# OpenROV_Controller_2_6.net
KiCad netlist of a schematic drawn in EAGLE
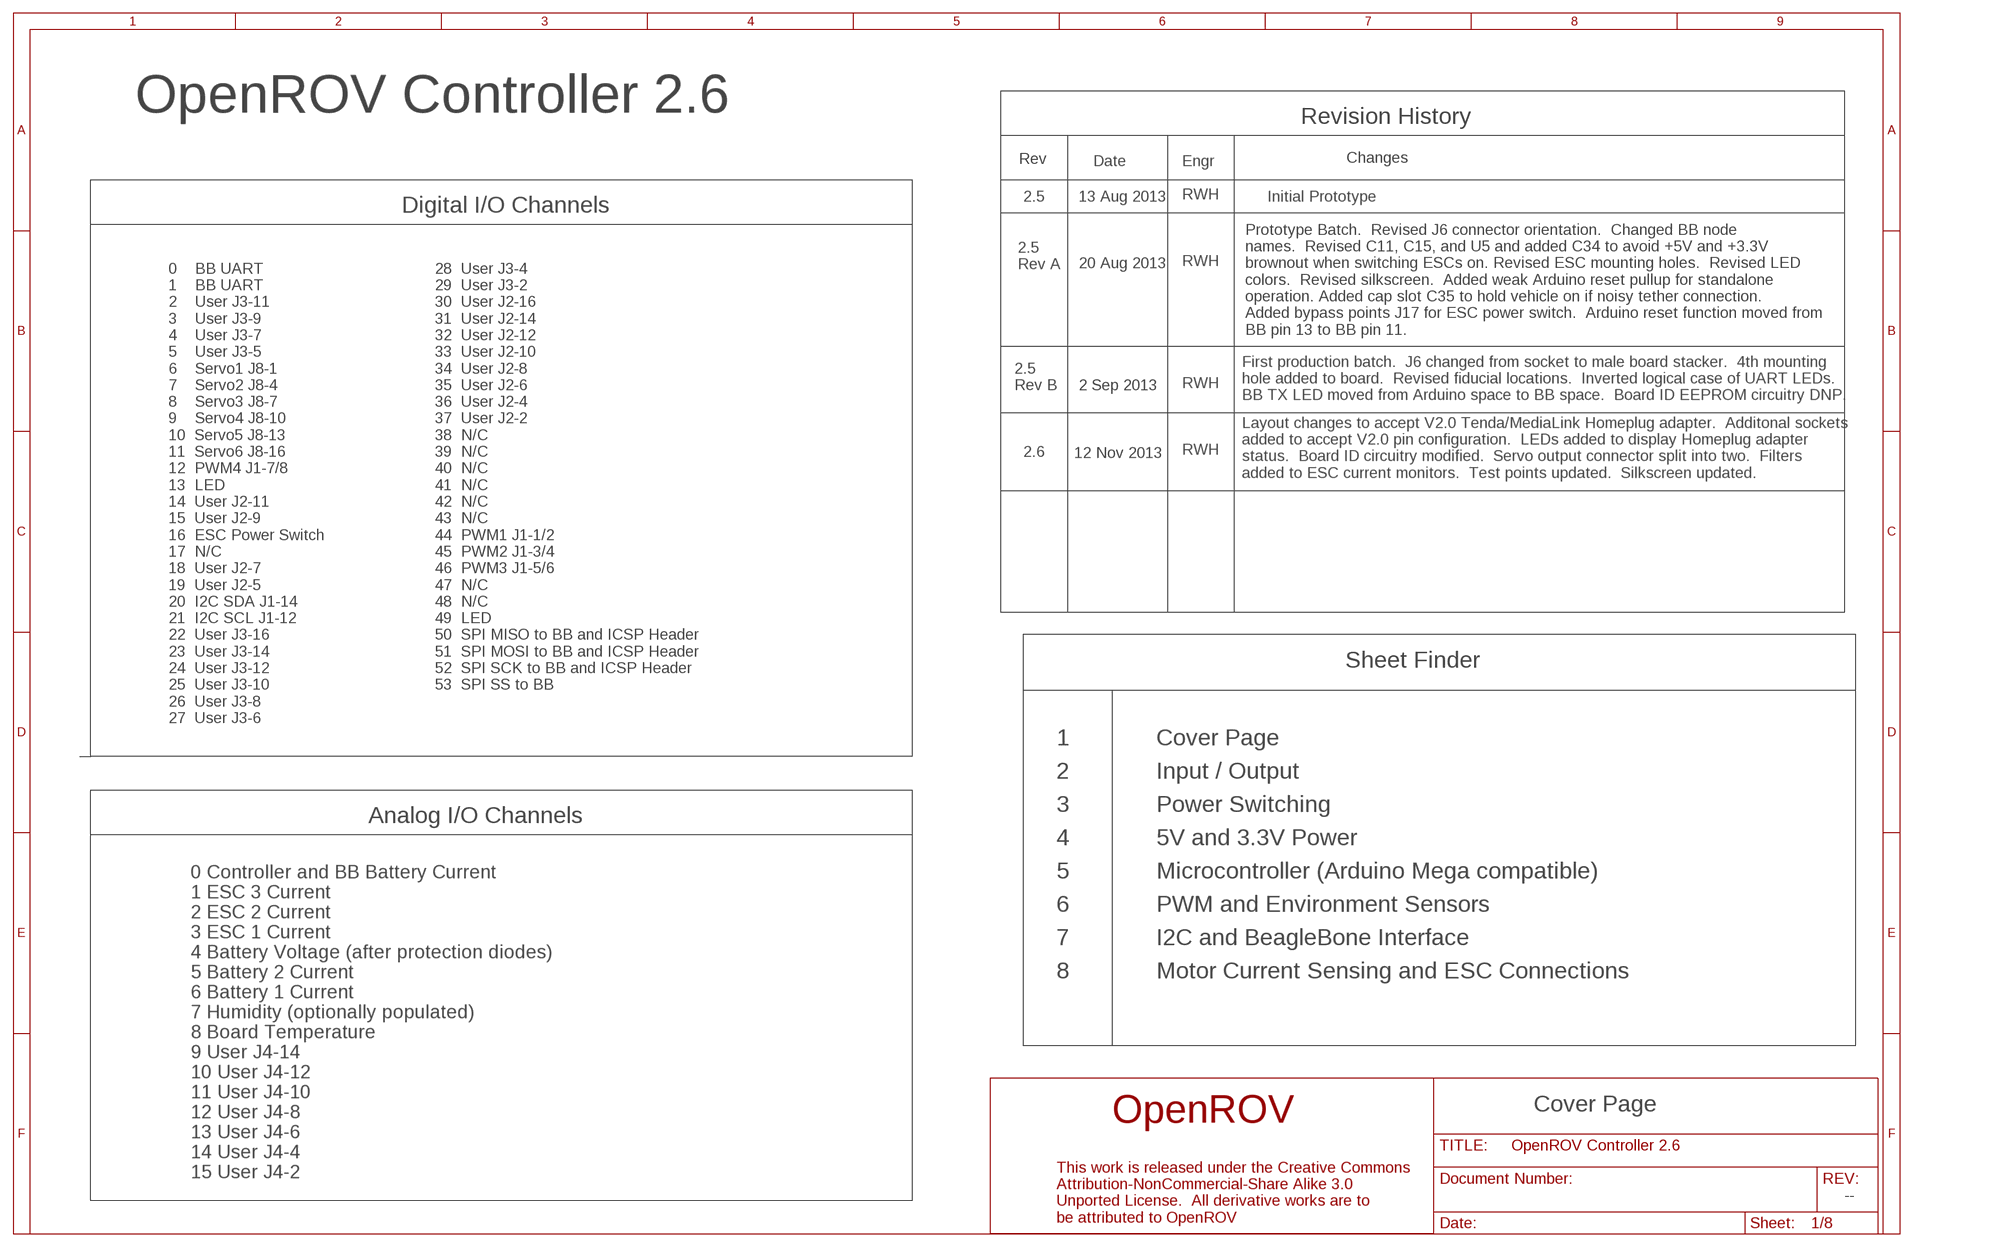
[diagram p0: schematic, sheet 1]
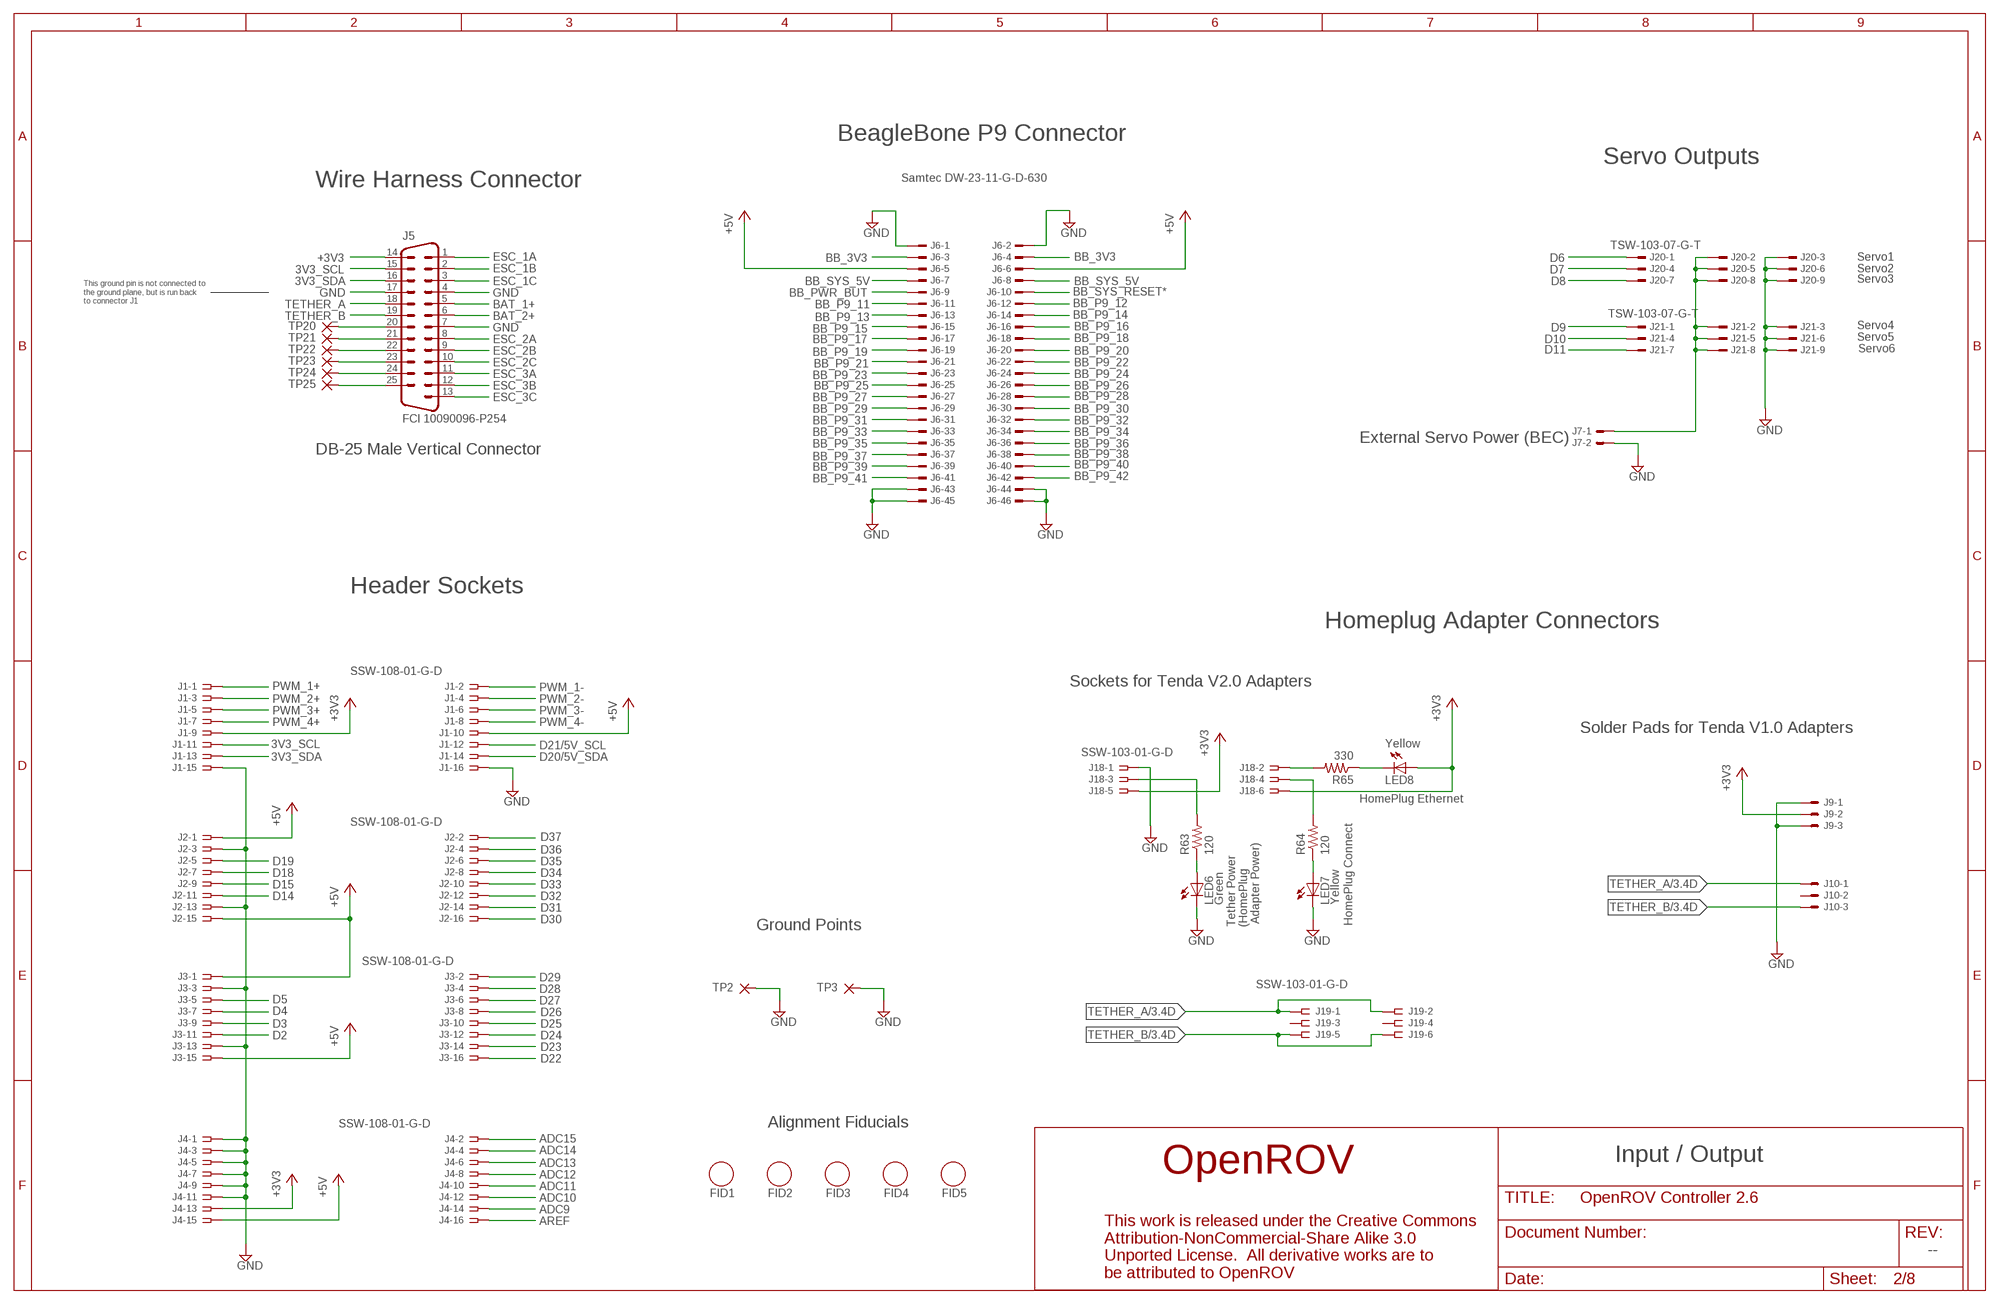
[diagram p1: schematic, sheet 2]
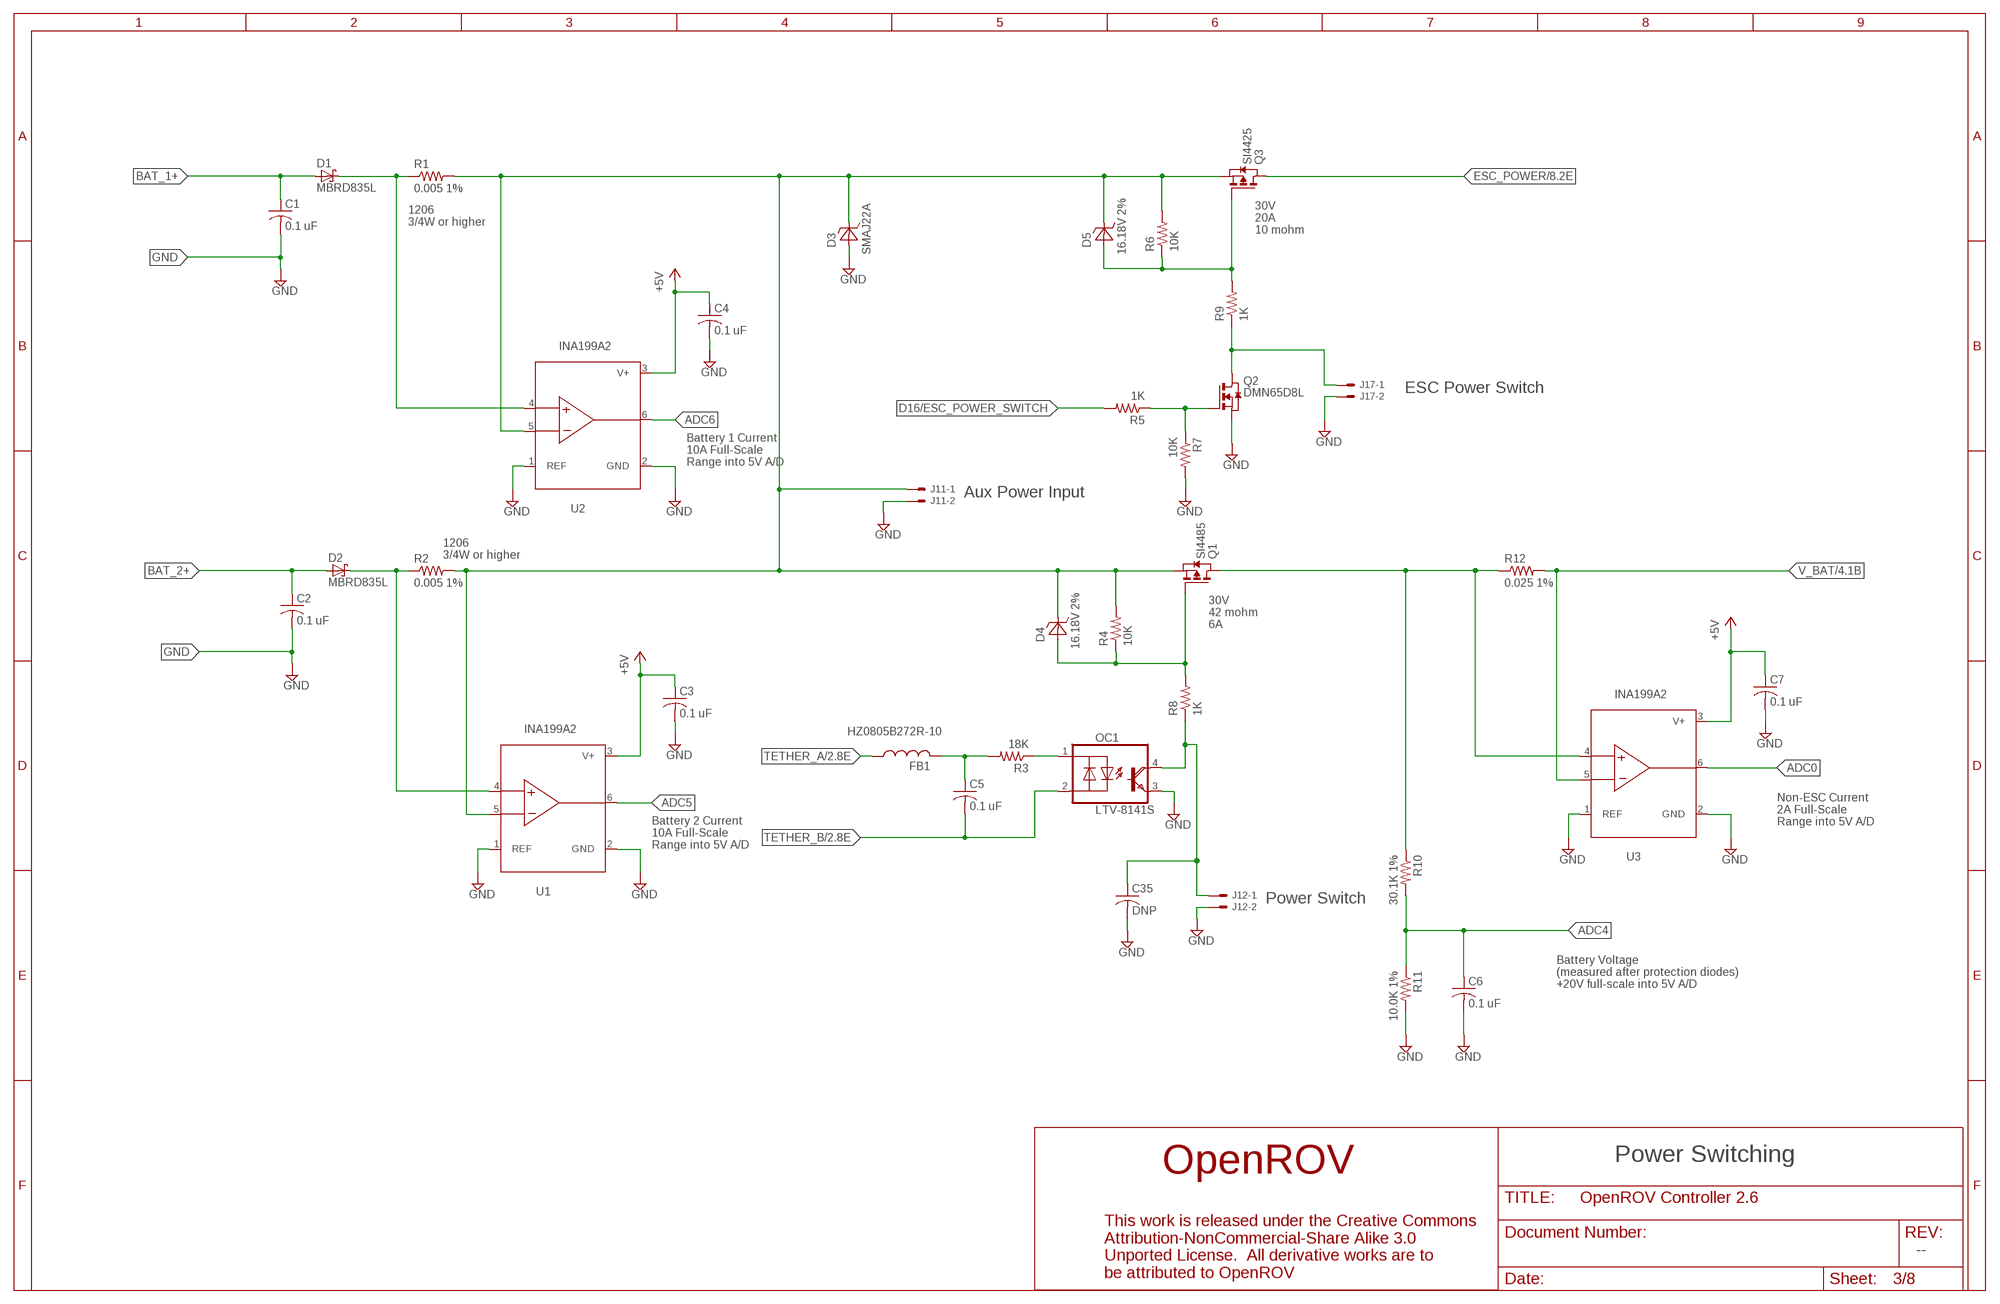
[diagram p2: schematic, sheet 3]
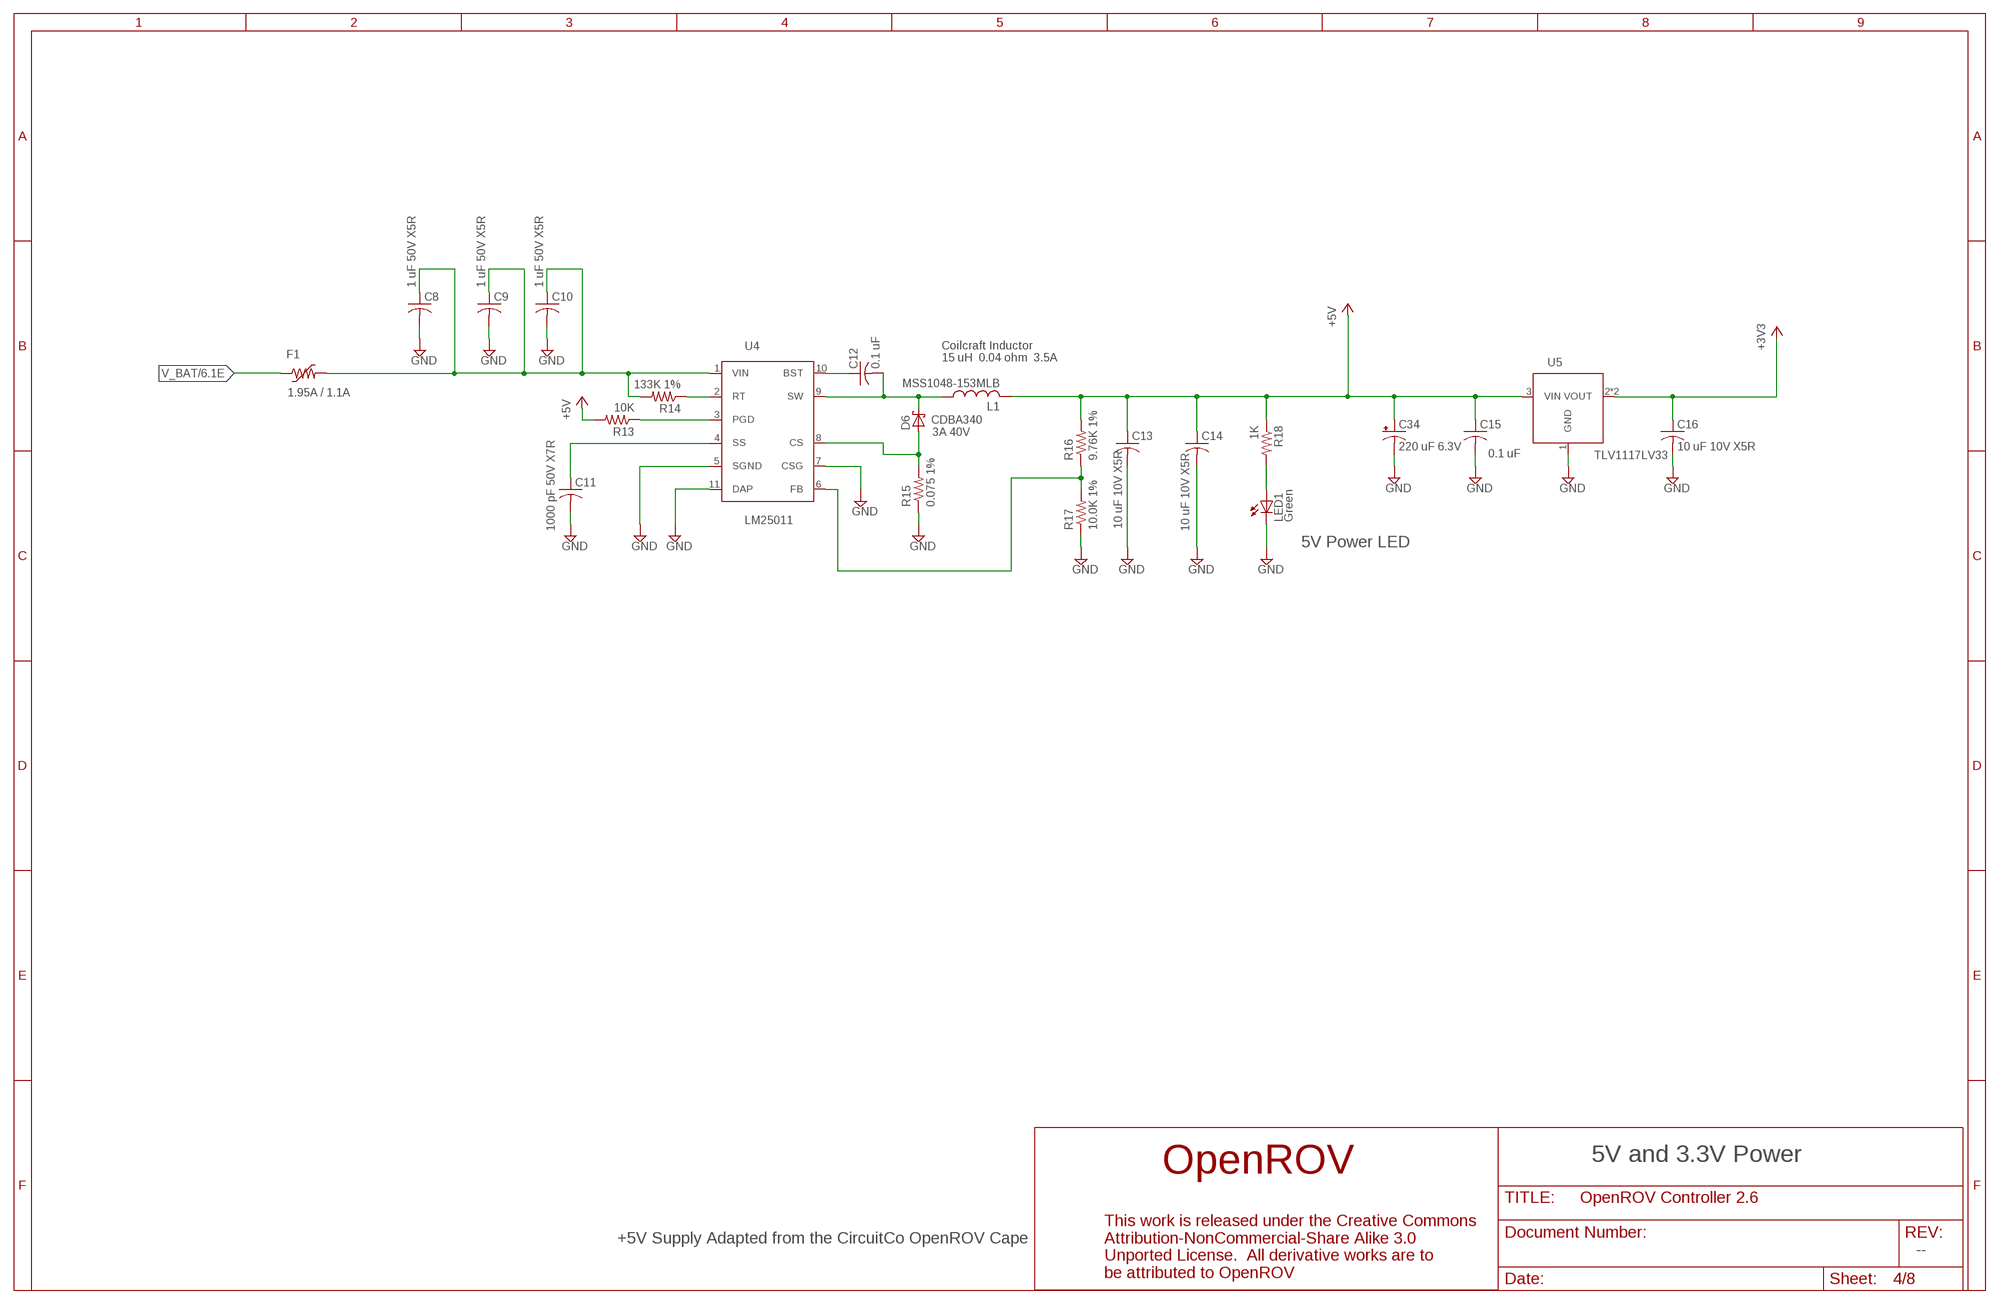
[diagram p3: schematic, sheet 4]
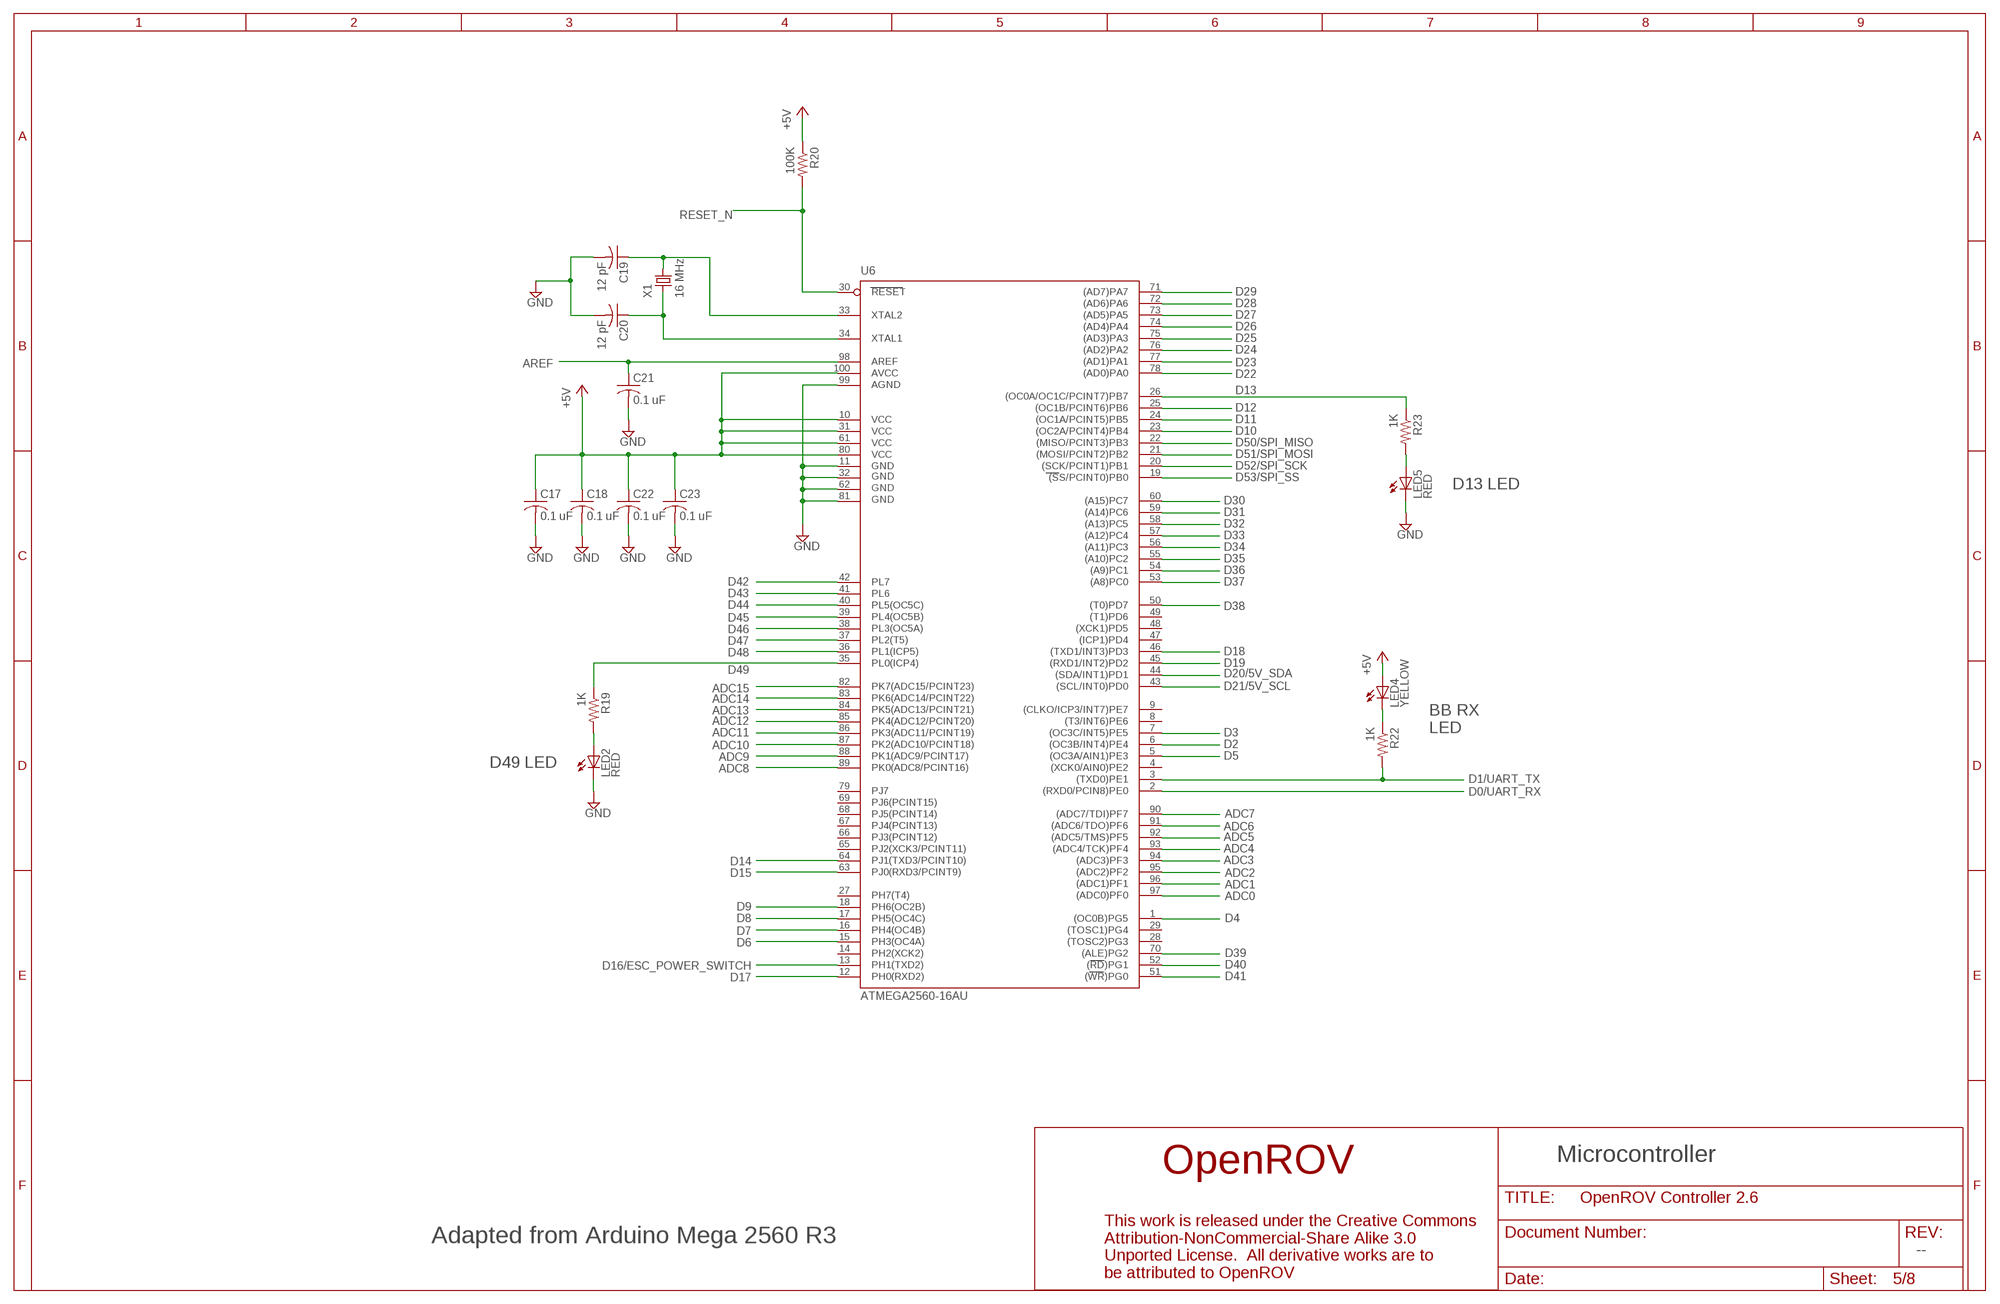
[diagram p4: schematic, sheet 5]
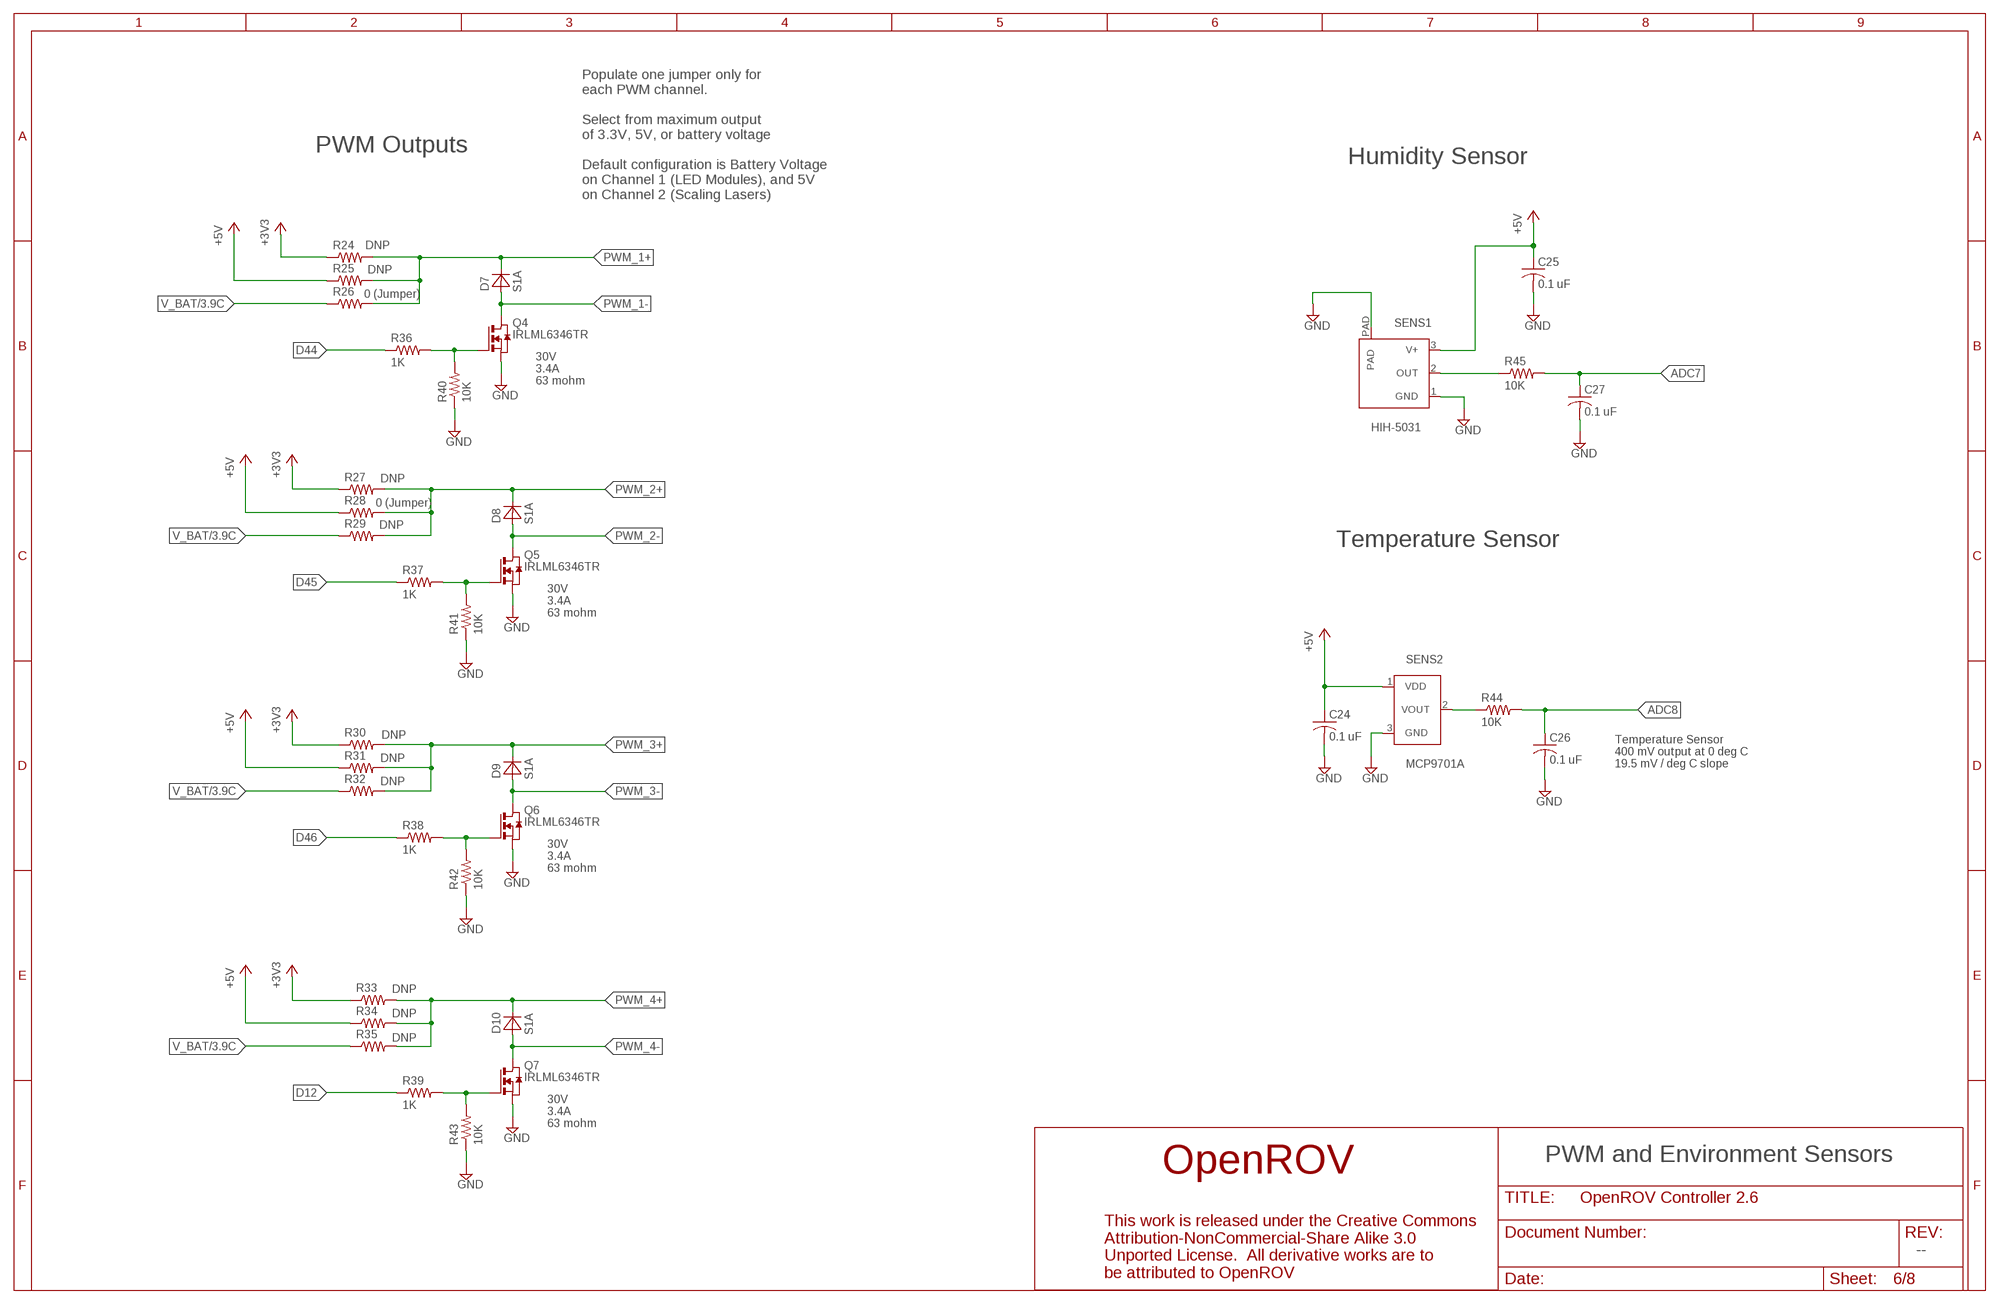
[diagram p5: schematic, sheet 6]
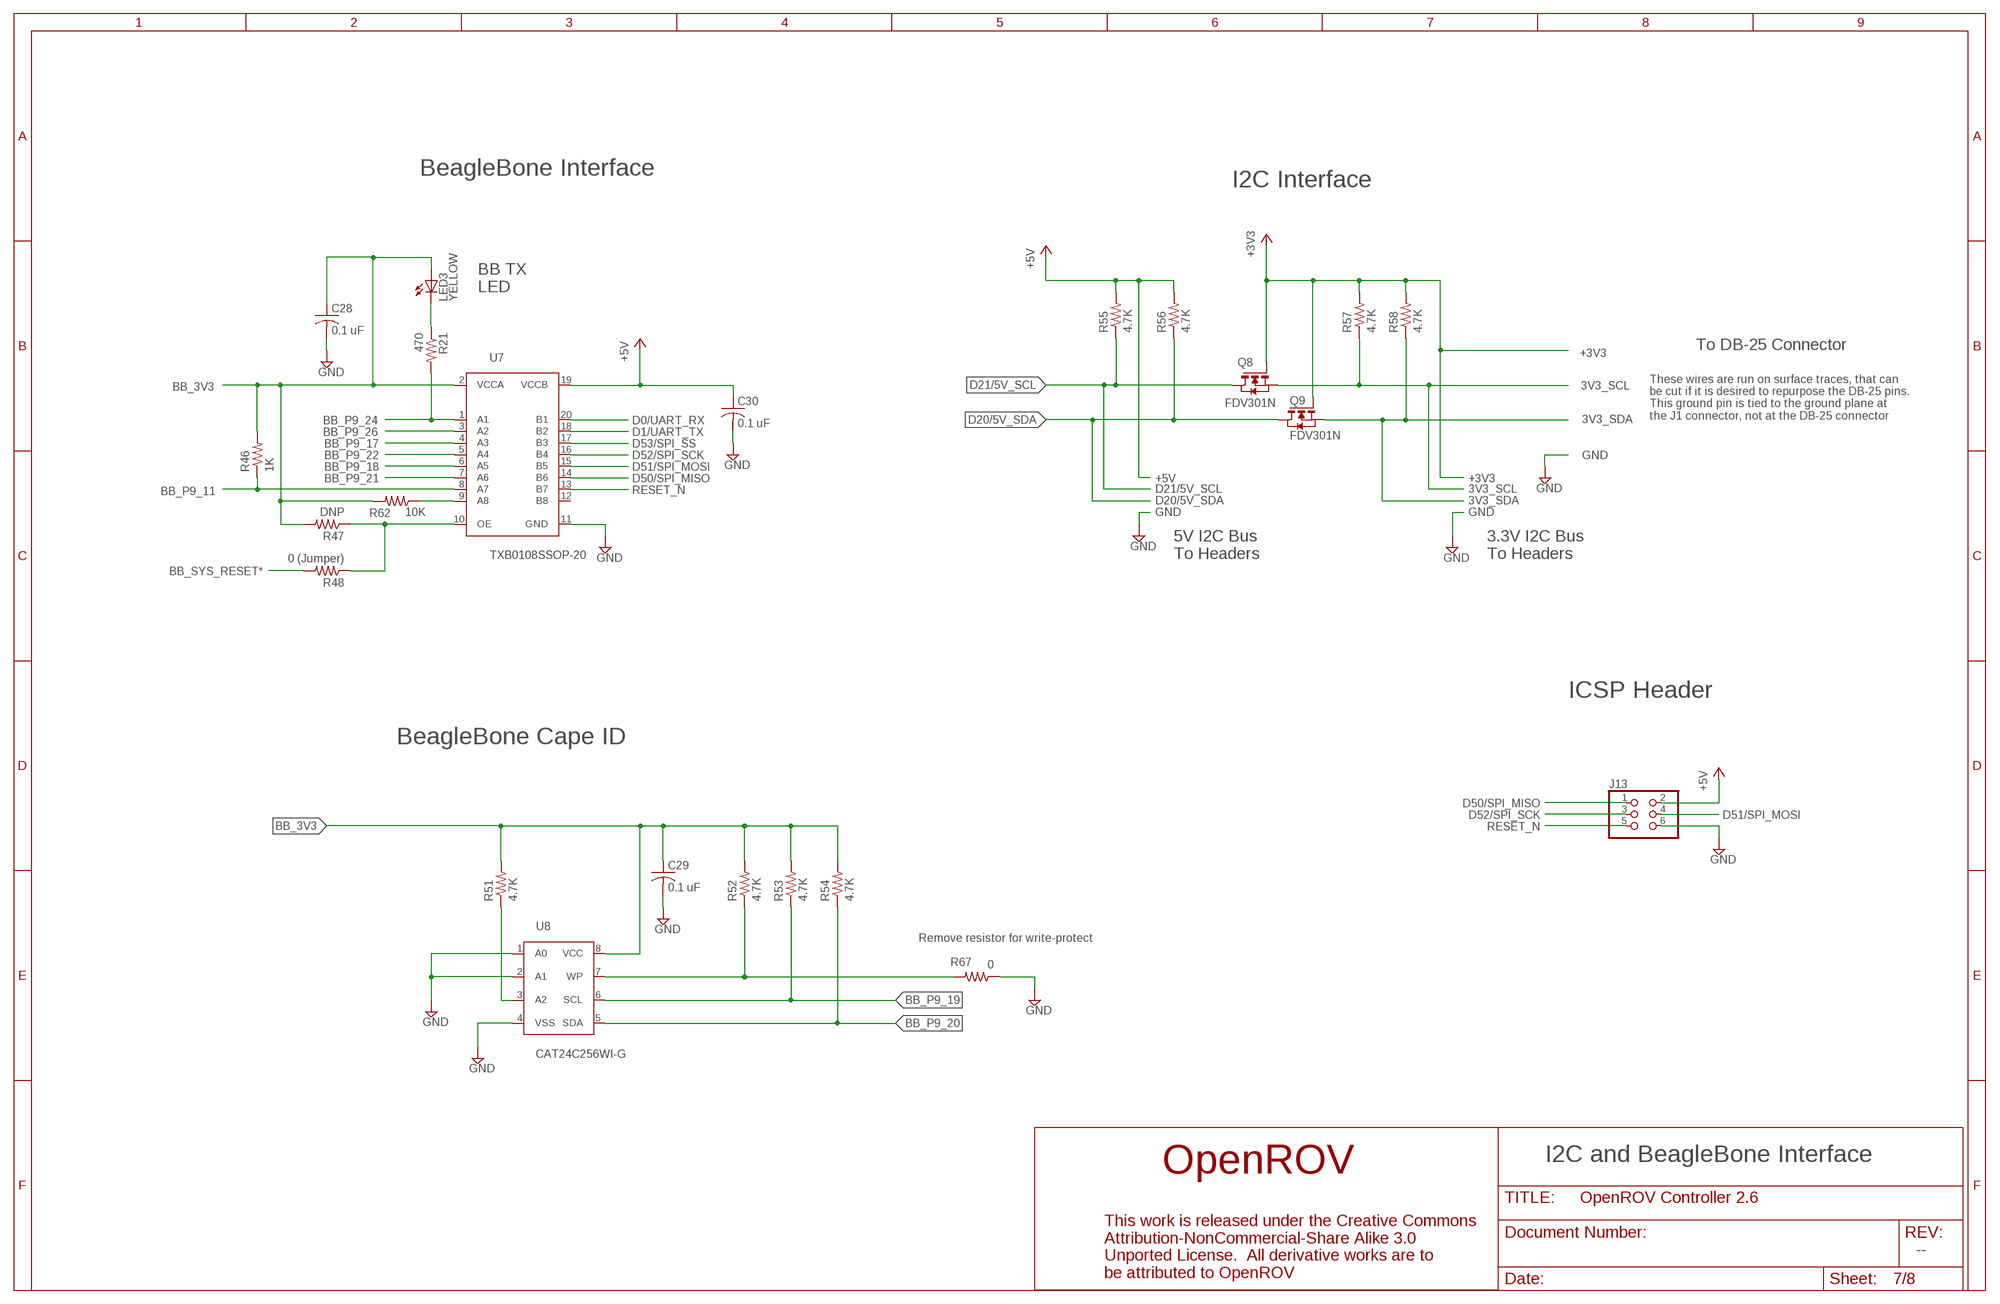
[diagram p6: schematic, sheet 7]
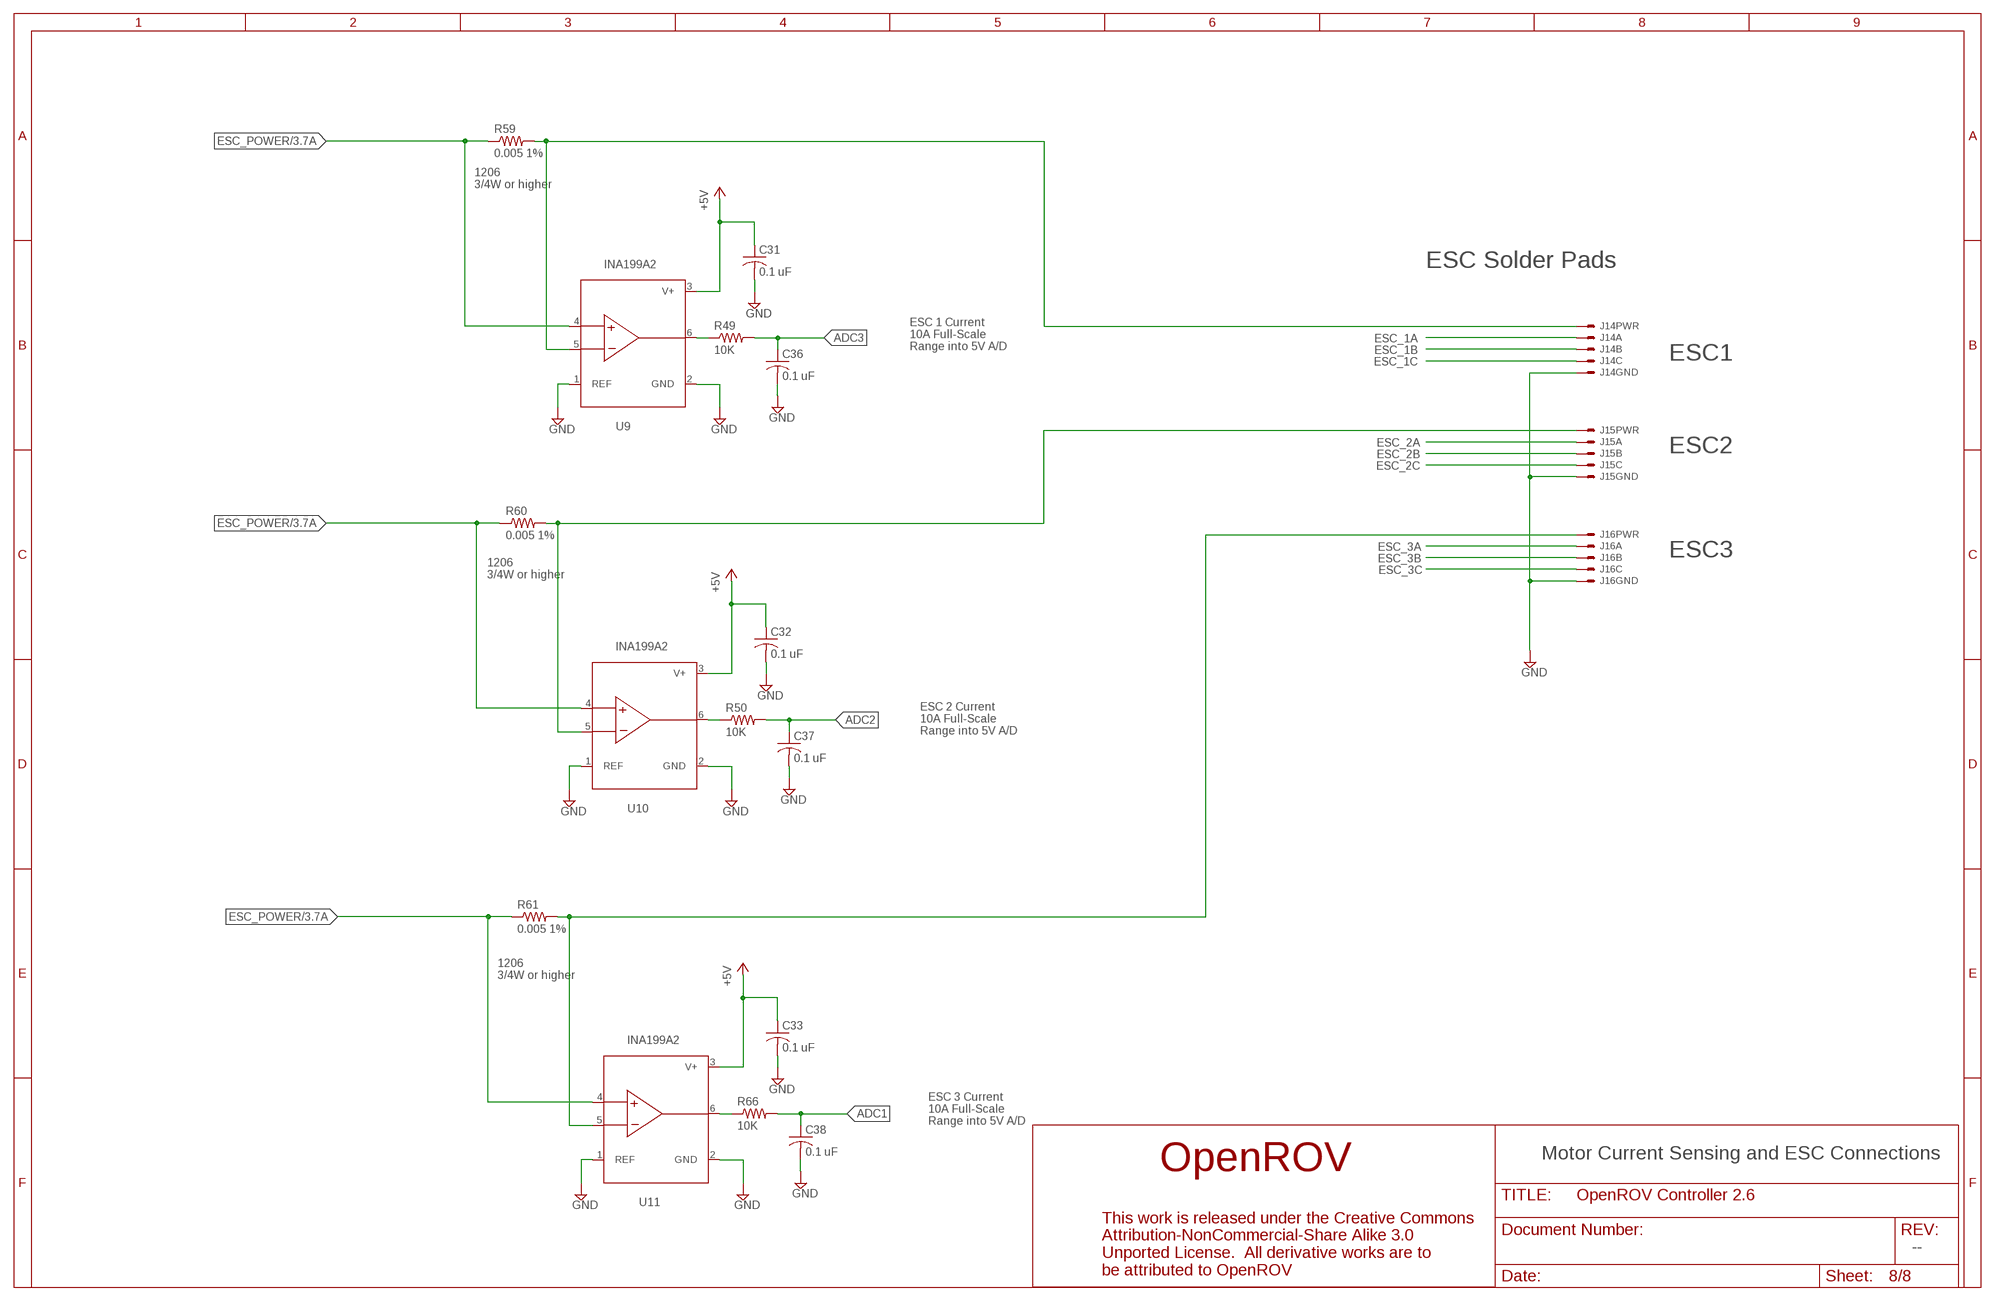
[diagram p7: schematic, sheet 8]

(export (version "E")
  (design (tool "Eeschema 10.0.6"))
  (components
    (comp (ref "FID1")
      (value "FIDUCIAL_1")
      (footprint "eagle-import:FIDUCIAL_1")
      (libsource (lib "eagle-import") (part "FIDUCIAL_1"))
    )
    (comp (ref "FID2")
      (value "FIDUCIAL_1")
      (footprint "eagle-import:FIDUCIAL_1")
      (libsource (lib "eagle-import") (part "FIDUCIAL_1"))
    )
    (comp (ref "FID3")
      (value "FIDUCIAL_1")
      (footprint "eagle-import:FIDUCIAL_1")
      (libsource (lib "eagle-import") (part "FIDUCIAL_1"))
    )
    (comp (ref "FID4")
      (value "FIDUCIAL_1")
      (footprint "eagle-import:FIDUCIAL_1")
      (libsource (lib "eagle-import") (part "FIDUCIAL_1"))
    )
    (comp (ref "FID5")
      (value "FIDUCIAL_1")
      (footprint "eagle-import:FIDUCIAL_1")
      (libsource (lib "eagle-import") (part "FIDUCIAL_1"))
    )
    (comp (ref "J1")
      (value "SSW-108-01-G-D")
      (footprint "eagle-import:SSW-108-02-S-D")
      (fields (field (name "MPN") "SSW-108-02-S-D"))
      (libsource (lib "eagle-import") (part "HDR_SOCKET_2X8"))
    )
    (comp (ref "J2")
      (value "SSW-108-01-G-D")
      (footprint "eagle-import:SSW-108-02-S-D")
      (fields (field (name "MPN") "SSW-108-02-S-D"))
      (libsource (lib "eagle-import") (part "HDR_SOCKET_2X8"))
    )
    (comp (ref "J3")
      (value "SSW-108-01-G-D")
      (footprint "eagle-import:SSW-108-02-S-D")
      (fields (field (name "MPN") "SSW-108-02-S-D"))
      (libsource (lib "eagle-import") (part "HDR_SOCKET_2X8"))
    )
    (comp (ref "J4")
      (value "SSW-108-01-G-D")
      (footprint "eagle-import:SSW-108-02-S-D")
      (fields (field (name "MPN") "SSW-108-02-S-D"))
      (libsource (lib "eagle-import") (part "HDR_SOCKET_2X8"))
    )
    (comp (ref "J5")
      (value "FCI 10090096-P254")
      (footprint "eagle-import:M25VP")
      (libsource (lib "eagle-import") (part "M25VP"))
    )
    (comp (ref "J6")
      (value "Samtec DW-23-11-G-D-630")
      (footprint "eagle-import:TSW-123-02-S-D")
      (libsource (lib "eagle-import") (part "BEAGLEBONE_PIN_HEADER"))
    )
    (comp (ref "J7")
      (value "HDR_1X2X0.100-ALT_SILK")
      (footprint "eagle-import:22-23-2021_ALT_SILK")
      (libsource (lib "eagle-import") (part "HDR_1X2X0.100-ALT_SILK"))
    )
    (comp (ref "J9")
      (value "HDR_1X3X0.100-ALT_SILK")
      (footprint "eagle-import:22-23-2031_ALT_SILK")
      (libsource (lib "eagle-import") (part "HDR_1X3X0.100-ALT_SILK"))
    )
    (comp (ref "J10")
      (value "HDR_1X3X0.100-ALT_SILK")
      (footprint "eagle-import:22-23-2031_ALT_SILK")
      (libsource (lib "eagle-import") (part "HDR_1X3X0.100-ALT_SILK"))
    )
    (comp (ref "J18")
      (value "SSW-103-01-G-D")
      (footprint "eagle-import:SSW-103-02-S-D")
      (fields (field (name "MPN") "SSW-103-02-S-D"))
      (libsource (lib "eagle-import") (part "HDR_SOCKET_2X3"))
    )
    (comp (ref "J19")
      (value "SSW-103-01-G-D")
      (footprint "eagle-import:SSW-103-02-S-D")
      (fields (field (name "MPN") "SSW-103-02-S-D"))
      (libsource (lib "eagle-import") (part "HDR_SOCKET_2X3"))
    )
    (comp (ref "J20")
      (value "TSW-103-07-G-T")
      (footprint "eagle-import:HDR_PINS_3X3")
      (libsource (lib "eagle-import") (part "HDR_PINS_3X3{dblquote}"))
    )
    (comp (ref "J21")
      (value "TSW-103-07-G-T")
      (footprint "eagle-import:HDR_PINS_3X3")
      (libsource (lib "eagle-import") (part "HDR_PINS_3X3{dblquote}"))
    )
    (comp (ref "LED6")
      (value "Green")
      (footprint "eagle-import:LED_CHIPLED_0603")
      (libsource (lib "eagle-import") (part "LED-0603"))
    )
    (comp (ref "LED7")
      (value "Yellow")
      (footprint "eagle-import:LED_CHIPLED_0603")
      (libsource (lib "eagle-import") (part "LED-0603"))
    )
    (comp (ref "LED8")
      (value "Yellow")
      (footprint "eagle-import:LED_CHIPLED_0603")
      (libsource (lib "eagle-import") (part "LED-0603"))
    )
    (comp (ref "R63")
      (value "120")
      (footprint "eagle-import:R0603")
      (libsource (lib "eagle-import") (part "RESISTOR-0603"))
    )
    (comp (ref "R64")
      (value "120")
      (footprint "eagle-import:R0603")
      (libsource (lib "eagle-import") (part "RESISTOR-0603"))
    )
    (comp (ref "R65")
      (value "330")
      (footprint "eagle-import:R0603")
      (libsource (lib "eagle-import") (part "RESISTOR-0603"))
    )
    (comp (ref "TP2")
      (value "TEST_PAD-1.0")
      (footprint "eagle-import:2.0_1.0")
      (libsource (lib "eagle-import") (part "TEST_PAD-1.0"))
    )
    (comp (ref "TP3")
      (value "TEST_PAD-1.0")
      (footprint "eagle-import:2.0_1.0")
      (libsource (lib "eagle-import") (part "TEST_PAD-1.0"))
    )
    (comp (ref "TP20")
      (value "TEST_PAD-1.0")
      (footprint "eagle-import:2.0_1.0")
      (libsource (lib "eagle-import") (part "TEST_PAD-1.0"))
    )
    (comp (ref "TP21")
      (value "TEST_PAD-1.0")
      (footprint "eagle-import:2.0_1.0")
      (libsource (lib "eagle-import") (part "TEST_PAD-1.0"))
    )
    (comp (ref "TP22")
      (value "TEST_PAD-1.0")
      (footprint "eagle-import:2.0_1.0")
      (libsource (lib "eagle-import") (part "TEST_PAD-1.0"))
    )
    (comp (ref "TP23")
      (value "TEST_PAD-1.0")
      (footprint "eagle-import:2.0_1.0")
      (libsource (lib "eagle-import") (part "TEST_PAD-1.0"))
    )
    (comp (ref "TP24")
      (value "TEST_PAD-1.0")
      (footprint "eagle-import:2.0_1.0")
      (libsource (lib "eagle-import") (part "TEST_PAD-1.0"))
    )
    (comp (ref "TP25")
      (value "TEST_PAD-1.0")
      (footprint "eagle-import:2.0_1.0")
      (libsource (lib "eagle-import") (part "TEST_PAD-1.0"))
    )
    (comp (ref "C1")
      (value "0.1 uF")
      (footprint "eagle-import:R0603")
      (libsource (lib "eagle-import") (part "CAP0603"))
    )
    (comp (ref "C2")
      (value "0.1 uF")
      (footprint "eagle-import:R0603")
      (libsource (lib "eagle-import") (part "CAP0603"))
    )
    (comp (ref "C3")
      (value "0.1 uF")
      (footprint "eagle-import:R0603")
      (libsource (lib "eagle-import") (part "CAP0603"))
    )
    (comp (ref "C4")
      (value "0.1 uF")
      (footprint "eagle-import:R0603")
      (libsource (lib "eagle-import") (part "CAP0603"))
    )
    (comp (ref "C5")
      (value "0.1 uF")
      (footprint "eagle-import:R0603")
      (libsource (lib "eagle-import") (part "CAP0603"))
    )
    (comp (ref "C6")
      (value "0.1 uF")
      (footprint "eagle-import:R0603")
      (libsource (lib "eagle-import") (part "CAP0603"))
    )
    (comp (ref "C7")
      (value "0.1 uF")
      (footprint "eagle-import:R0603")
      (libsource (lib "eagle-import") (part "CAP0603"))
    )
    (comp (ref "C35")
      (value "DNP")
      (footprint "eagle-import:R0805")
      (libsource (lib "eagle-import") (part "CAP0805"))
    )
    (comp (ref "D1")
      (value "MBRD835L")
      (footprint "eagle-import:DPAK")
      (libsource (lib "eagle-import") (part "SCHOTTKYDPAK"))
    )
    (comp (ref "D2")
      (value "MBRD835L")
      (footprint "eagle-import:DPAK")
      (libsource (lib "eagle-import") (part "SCHOTTKYDPAK"))
    )
    (comp (ref "D3")
      (value "SMAJ22A")
      (footprint "eagle-import:DO214AC")
      (libsource (lib "eagle-import") (part "ZENER-TVSDO-214AC"))
    )
    (comp (ref "D4")
      (value "16.18V 2%")
      (footprint "eagle-import:SOD323")
      (libsource (lib "eagle-import") (part "ZENER-TVSSOD323"))
    )
    (comp (ref "D5")
      (value "16.18V 2%")
      (footprint "eagle-import:SOD323")
      (libsource (lib "eagle-import") (part "ZENER-TVSSOD323"))
    )
    (comp (ref "FB1")
      (value "HZ0805B272R-10")
      (footprint "eagle-import:R0805")
      (libsource (lib "eagle-import") (part "FERRITESIZE_0805"))
    )
    (comp (ref "J11")
      (value "HDR_1X2X0.100-ALT_SILK")
      (footprint "eagle-import:22-23-2021_ALT_SILK")
      (libsource (lib "eagle-import") (part "HDR_1X2X0.100-ALT_SILK"))
    )
    (comp (ref "J12")
      (value "HDR_1X2X0.100-ALT_SILK")
      (footprint "eagle-import:22-23-2021_ALT_SILK")
      (libsource (lib "eagle-import") (part "HDR_1X2X0.100-ALT_SILK"))
    )
    (comp (ref "J17")
      (value "HDR_1X2X0.100-ALT_SILK")
      (footprint "eagle-import:22-23-2021_ALT_SILK")
      (libsource (lib "eagle-import") (part "HDR_1X2X0.100-ALT_SILK"))
    )
    (comp (ref "OC1")
      (value "LTV-8141S")
      (footprint "eagle-import:DIL4-SMD")
      (libsource (lib "eagle-import") (part "LTV-8141S"))
    )
    (comp (ref "Q1")
      (value "SI4485")
      (footprint "eagle-import:SO8")
      (libsource (lib "eagle-import") (part "PMOS-FET"))
    )
    (comp (ref "Q2")
      (value "DMN65D8L")
      (footprint "eagle-import:SOT23")
      (libsource (lib "eagle-import") (part "NMOS-FETSOT23"))
    )
    (comp (ref "Q3")
      (value "SI4425")
      (footprint "eagle-import:SO8")
      (libsource (lib "eagle-import") (part "PMOS-FET"))
    )
    (comp (ref "R1")
      (value "0.005 1%")
      (footprint "eagle-import:R1206")
      (libsource (lib "eagle-import") (part "RESISTOR-1206"))
    )
    (comp (ref "R2")
      (value "0.005 1%")
      (footprint "eagle-import:R1206")
      (libsource (lib "eagle-import") (part "RESISTOR-1206"))
    )
    (comp (ref "R3")
      (value "18K")
      (footprint "eagle-import:R0603")
      (libsource (lib "eagle-import") (part "RESISTOR-0603"))
    )
    (comp (ref "R4")
      (value "10K")
      (footprint "eagle-import:R0603")
      (libsource (lib "eagle-import") (part "RESISTOR-0603"))
    )
    (comp (ref "R5")
      (value "1K")
      (footprint "eagle-import:R0603")
      (libsource (lib "eagle-import") (part "RESISTOR-0603"))
    )
    (comp (ref "R6")
      (value "10K")
      (footprint "eagle-import:R0603")
      (libsource (lib "eagle-import") (part "RESISTOR-0603"))
    )
    (comp (ref "R7")
      (value "10K")
      (footprint "eagle-import:R0603")
      (libsource (lib "eagle-import") (part "RESISTOR-0603"))
    )
    (comp (ref "R8")
      (value "1K")
      (footprint "eagle-import:R0603")
      (libsource (lib "eagle-import") (part "RESISTOR-0603"))
    )
    (comp (ref "R9")
      (value "1K")
      (footprint "eagle-import:R0603")
      (libsource (lib "eagle-import") (part "RESISTOR-0603"))
    )
    (comp (ref "R10")
      (value "30.1K 1%")
      (footprint "eagle-import:R0603")
      (libsource (lib "eagle-import") (part "RESISTOR-0603"))
    )
    (comp (ref "R11")
      (value "10.0K 1%")
      (footprint "eagle-import:R0603")
      (libsource (lib "eagle-import") (part "RESISTOR-0603"))
    )
    (comp (ref "R12")
      (value "0.025 1%")
      (footprint "eagle-import:R0805")
      (libsource (lib "eagle-import") (part "RESISTOR-0805"))
    )
    (comp (ref "U1")
      (value "INA199A2")
      (footprint "eagle-import:SC70-6L")
      (libsource (lib "eagle-import") (part "INA199"))
    )
    (comp (ref "U2")
      (value "INA199A2")
      (footprint "eagle-import:SC70-6L")
      (libsource (lib "eagle-import") (part "INA199"))
    )
    (comp (ref "U3")
      (value "INA199A2")
      (footprint "eagle-import:SC70-6L")
      (libsource (lib "eagle-import") (part "INA199"))
    )
    (comp (ref "C31")
      (value "0.1 uF")
      (footprint "eagle-import:R0603")
      (libsource (lib "eagle-import") (part "CAP0603"))
    )
    (comp (ref "C32")
      (value "0.1 uF")
      (footprint "eagle-import:R0603")
      (libsource (lib "eagle-import") (part "CAP0603"))
    )
    (comp (ref "C33")
      (value "0.1 uF")
      (footprint "eagle-import:R0603")
      (libsource (lib "eagle-import") (part "CAP0603"))
    )
    (comp (ref "C36")
      (value "0.1 uF")
      (footprint "eagle-import:R0603")
      (libsource (lib "eagle-import") (part "CAP0603"))
    )
    (comp (ref "C37")
      (value "0.1 uF")
      (footprint "eagle-import:R0603")
      (libsource (lib "eagle-import") (part "CAP0603"))
    )
    (comp (ref "C38")
      (value "0.1 uF")
      (footprint "eagle-import:R0603")
      (libsource (lib "eagle-import") (part "CAP0603"))
    )
    (comp (ref "J14")
      (value "ESC_PADS-0.156_ALT")
      (footprint "eagle-import:ESC-PADS-.156-ALT_SILK")
      (libsource (lib "eagle-import") (part "ESC_PADS-0.156_ALT"))
    )
    (comp (ref "J15")
      (value "ESC_PADS-0.156_ALT")
      (footprint "eagle-import:ESC-PADS-.156-ALT_SILK")
      (libsource (lib "eagle-import") (part "ESC_PADS-0.156_ALT"))
    )
    (comp (ref "J16")
      (value "ESC_PADS-0.156_ALT")
      (footprint "eagle-import:ESC-PADS-.156-ALT_SILK")
      (libsource (lib "eagle-import") (part "ESC_PADS-0.156_ALT"))
    )
    (comp (ref "R49")
      (value "10K")
      (footprint "eagle-import:R0603")
      (libsource (lib "eagle-import") (part "RESISTOR-0603"))
    )
    (comp (ref "R50")
      (value "10K")
      (footprint "eagle-import:R0603")
      (libsource (lib "eagle-import") (part "RESISTOR-0603"))
    )
    (comp (ref "R59")
      (value "0.005 1%")
      (footprint "eagle-import:R1206")
      (libsource (lib "eagle-import") (part "RESISTOR-1206"))
    )
    (comp (ref "R60")
      (value "0.005 1%")
      (footprint "eagle-import:R1206")
      (libsource (lib "eagle-import") (part "RESISTOR-1206"))
    )
    (comp (ref "R61")
      (value "0.005 1%")
      (footprint "eagle-import:R1206")
      (libsource (lib "eagle-import") (part "RESISTOR-1206"))
    )
    (comp (ref "R66")
      (value "10K")
      (footprint "eagle-import:R0603")
      (libsource (lib "eagle-import") (part "RESISTOR-0603"))
    )
    (comp (ref "U9")
      (value "INA199A2")
      (footprint "eagle-import:SC70-6L")
      (libsource (lib "eagle-import") (part "INA199"))
    )
    (comp (ref "U10")
      (value "INA199A2")
      (footprint "eagle-import:SC70-6L")
      (libsource (lib "eagle-import") (part "INA199"))
    )
    (comp (ref "U11")
      (value "INA199A2")
      (footprint "eagle-import:SC70-6L")
      (libsource (lib "eagle-import") (part "INA199"))
    )
    (comp (ref "C17")
      (value "0.1 uF")
      (footprint "eagle-import:R0603")
      (libsource (lib "eagle-import") (part "CAP0603"))
    )
    (comp (ref "C18")
      (value "0.1 uF")
      (footprint "eagle-import:R0603")
      (libsource (lib "eagle-import") (part "CAP0603"))
    )
    (comp (ref "C19")
      (value "12 pF")
      (footprint "eagle-import:R0603")
      (libsource (lib "eagle-import") (part "CAP0603"))
    )
    (comp (ref "C20")
      (value "12 pF")
      (footprint "eagle-import:R0603")
      (libsource (lib "eagle-import") (part "CAP0603"))
    )
    (comp (ref "C21")
      (value "0.1 uF")
      (footprint "eagle-import:R0603")
      (libsource (lib "eagle-import") (part "CAP0603"))
    )
    (comp (ref "C22")
      (value "0.1 uF")
      (footprint "eagle-import:R0603")
      (libsource (lib "eagle-import") (part "CAP0603"))
    )
    (comp (ref "C23")
      (value "0.1 uF")
      (footprint "eagle-import:R0603")
      (libsource (lib "eagle-import") (part "CAP0603"))
    )
    (comp (ref "LED2")
      (value "RED")
      (footprint "eagle-import:LED_CHIPLED_0603")
      (libsource (lib "eagle-import") (part "LED-0603"))
    )
    (comp (ref "LED4")
      (value "YELLOW")
      (footprint "eagle-import:LED_CHIPLED_0603")
      (libsource (lib "eagle-import") (part "LED-0603"))
    )
    (comp (ref "LED5")
      (value "RED")
      (footprint "eagle-import:LED_CHIPLED_0603")
      (libsource (lib "eagle-import") (part "LED-0603"))
    )
    (comp (ref "R19")
      (value "1K")
      (footprint "eagle-import:R0603")
      (libsource (lib "eagle-import") (part "RESISTOR-0603"))
    )
    (comp (ref "R20")
      (value "100K")
      (footprint "eagle-import:R0603")
      (libsource (lib "eagle-import") (part "RESISTOR-0603"))
    )
    (comp (ref "R22")
      (value "1K")
      (footprint "eagle-import:R0603")
      (libsource (lib "eagle-import") (part "RESISTOR-0603"))
    )
    (comp (ref "R23")
      (value "1K")
      (footprint "eagle-import:R0603")
      (libsource (lib "eagle-import") (part "RESISTOR-0603"))
    )
    (comp (ref "U6")
      (value "ATMEGA2560-16AU")
      (footprint "eagle-import:SMARTPRJ_TQFP100")
      (libsource (lib "eagle-import") (part "SMARTPRJ_ATMEGA2560AU2560-16"))
    )
    (comp (ref "X1")
      (value "16 MHz")
      (footprint "eagle-import:DISCRETE_2P-SMD-5X3.2")
      (libsource (lib "eagle-import") (part "CRYSTAL-53.2"))
    )
    (comp (ref "C8")
      (value "1 uF 50V X5R")
      (footprint "eagle-import:R0805")
      (libsource (lib "eagle-import") (part "CAP0805"))
    )
    (comp (ref "C9")
      (value "1 uF 50V X5R")
      (footprint "eagle-import:R0805")
      (libsource (lib "eagle-import") (part "CAP0805"))
    )
    (comp (ref "C10")
      (value "1 uF 50V X5R")
      (footprint "eagle-import:R0805")
      (libsource (lib "eagle-import") (part "CAP0805"))
    )
    (comp (ref "C11")
      (value "1000 pF 50V X7R")
      (footprint "eagle-import:R0603")
      (libsource (lib "eagle-import") (part "CAP0603"))
    )
    (comp (ref "C12")
      (value "0.1 uF")
      (footprint "eagle-import:R0603")
      (libsource (lib "eagle-import") (part "CAP0603"))
    )
    (comp (ref "C13")
      (value "10 uF 10V X5R")
      (footprint "eagle-import:R0805")
      (libsource (lib "eagle-import") (part "CAP0805"))
    )
    (comp (ref "C14")
      (value "10 uF 10V X5R")
      (footprint "eagle-import:R0805")
      (libsource (lib "eagle-import") (part "CAP0805"))
    )
    (comp (ref "C15")
      (value "0.1 uF")
      (footprint "eagle-import:R0603")
      (libsource (lib "eagle-import") (part "CAP0603"))
    )
    (comp (ref "C16")
      (value "10 uF 10V X5R")
      (footprint "eagle-import:R0805")
      (libsource (lib "eagle-import") (part "CAP0805"))
    )
    (comp (ref "C34")
      (value "220 uF 6.3V")
      (footprint "eagle-import:KEMET_B-CAPACITOR")
      (libsource (lib "eagle-import") (part "CAP-POLARIZED-B_CASE"))
    )
    (comp (ref "D6")
      (value "CDBA340")
      (footprint "eagle-import:DO214AC")
      (libsource (lib "eagle-import") (part "SCHOTTKYDO214AC"))
    )
    (comp (ref "F1")
      (value "1.95A / 1.1A")
      (footprint "eagle-import:R1812")
      (libsource (lib "eagle-import") (part "POLYFUSE-1812"))
    )
    (comp (ref "L1")
      (value "MSS1048-153MLB")
      (footprint "eagle-import:MSS1048")
      (libsource (lib "eagle-import") (part "INDUCTOR-MSS1048"))
    )
    (comp (ref "LED1")
      (value "Green")
      (footprint "eagle-import:LED_CHIPLED_0603")
      (libsource (lib "eagle-import") (part "LED-0603"))
    )
    (comp (ref "R13")
      (value "10K")
      (footprint "eagle-import:R0603")
      (libsource (lib "eagle-import") (part "RESISTOR-0603"))
    )
    (comp (ref "R14")
      (value "133K 1%")
      (footprint "eagle-import:R0603")
      (libsource (lib "eagle-import") (part "RESISTOR-0603"))
    )
    (comp (ref "R15")
      (value "0.075 1%")
      (footprint "eagle-import:R1210")
      (libsource (lib "eagle-import") (part "RESISTOR-1210"))
    )
    (comp (ref "R16")
      (value "9.76K 1%")
      (footprint "eagle-import:R0603")
      (libsource (lib "eagle-import") (part "RESISTOR-0603"))
    )
    (comp (ref "R17")
      (value "10.0K 1%")
      (footprint "eagle-import:R0603")
      (libsource (lib "eagle-import") (part "RESISTOR-0603"))
    )
    (comp (ref "R18")
      (value "1K")
      (footprint "eagle-import:R0603")
      (libsource (lib "eagle-import") (part "RESISTOR-0603"))
    )
    (comp (ref "U4")
      (value "LM25011")
      (footprint "eagle-import:VSSOP-10")
      (libsource (lib "eagle-import") (part "LM25011"))
    )
    (comp (ref "U5")
      (value "TLV1117LV33")
      (footprint "eagle-import:SOT223")
      (libsource (lib "eagle-import") (part "AP1117SOT223"))
    )
    (comp (ref "C28")
      (value "0.1 uF")
      (footprint "eagle-import:R0603")
      (libsource (lib "eagle-import") (part "CAP0603"))
    )
    (comp (ref "C29")
      (value "0.1 uF")
      (footprint "eagle-import:R0603")
      (libsource (lib "eagle-import") (part "CAP0603"))
    )
    (comp (ref "C30")
      (value "0.1 uF")
      (footprint "eagle-import:R0603")
      (libsource (lib "eagle-import") (part "CAP0603"))
    )
    (comp (ref "J13")
      (value "HDR_PINS_2X3")
      (footprint "eagle-import:HDR_PINS_2X3")
      (libsource (lib "eagle-import") (part "HDR_PINS_2X3"))
    )
    (comp (ref "LED3")
      (value "YELLOW")
      (footprint "eagle-import:LED_CHIPLED_0603")
      (libsource (lib "eagle-import") (part "LED-0603"))
    )
    (comp (ref "Q8")
      (value "FDV301N")
      (footprint "eagle-import:SOT23")
      (libsource (lib "eagle-import") (part "NMOS-FETSOT23"))
    )
    (comp (ref "Q9")
      (value "FDV301N")
      (footprint "eagle-import:SOT23")
      (libsource (lib "eagle-import") (part "NMOS-FETSOT23"))
    )
    (comp (ref "R21")
      (value "470")
      (footprint "eagle-import:R0603")
      (libsource (lib "eagle-import") (part "RESISTOR-0603"))
    )
    (comp (ref "R46")
      (value "1K")
      (footprint "eagle-import:R0603")
      (libsource (lib "eagle-import") (part "RESISTOR-0603"))
    )
    (comp (ref "R47")
      (value "DNP")
      (footprint "eagle-import:R0603")
      (libsource (lib "eagle-import") (part "RESISTOR-0603"))
    )
    (comp (ref "R48")
      (value "0 (Jumper)")
      (footprint "eagle-import:R0603")
      (libsource (lib "eagle-import") (part "RESISTOR-0603"))
    )
    (comp (ref "R51")
      (value "4.7K")
      (footprint "eagle-import:R0603")
      (libsource (lib "eagle-import") (part "RESISTOR-0603"))
    )
    (comp (ref "R52")
      (value "4.7K")
      (footprint "eagle-import:R0603")
      (libsource (lib "eagle-import") (part "RESISTOR-0603"))
    )
    (comp (ref "R53")
      (value "4.7K")
      (footprint "eagle-import:R0603")
      (libsource (lib "eagle-import") (part "RESISTOR-0603"))
    )
    (comp (ref "R54")
      (value "4.7K")
      (footprint "eagle-import:R0603")
      (libsource (lib "eagle-import") (part "RESISTOR-0603"))
    )
    (comp (ref "R55")
      (value "4.7K")
      (footprint "eagle-import:R0603")
      (libsource (lib "eagle-import") (part "RESISTOR-0603"))
    )
    (comp (ref "R56")
      (value "4.7K")
      (footprint "eagle-import:R0603")
      (libsource (lib "eagle-import") (part "RESISTOR-0603"))
    )
    (comp (ref "R57")
      (value "4.7K")
      (footprint "eagle-import:R0603")
      (libsource (lib "eagle-import") (part "RESISTOR-0603"))
    )
    (comp (ref "R58")
      (value "4.7K")
      (footprint "eagle-import:R0603")
      (libsource (lib "eagle-import") (part "RESISTOR-0603"))
    )
    (comp (ref "R62")
      (value "10K")
      (footprint "eagle-import:R0603")
      (libsource (lib "eagle-import") (part "RESISTOR-0603"))
    )
    (comp (ref "R67")
      (value "0")
      (footprint "eagle-import:R0603")
      (libsource (lib "eagle-import") (part "RESISTOR-0603"))
    )
    (comp (ref "U7")
      (value "TXB0108SSOP-20")
      (footprint "eagle-import:SSOP-20")
      (libsource (lib "eagle-import") (part "TXB0108SSOP-20"))
    )
    (comp (ref "U8")
      (value "CAT24C256WI-G")
      (footprint "eagle-import:SO8")
      (libsource (lib "eagle-import") (part "CAT24C256WI-G"))
    )
    (comp (ref "C24")
      (value "0.1 uF")
      (footprint "eagle-import:R0603")
      (libsource (lib "eagle-import") (part "CAP0603"))
    )
    (comp (ref "C25")
      (value "0.1 uF")
      (footprint "eagle-import:R0603")
      (libsource (lib "eagle-import") (part "CAP0603"))
    )
    (comp (ref "C26")
      (value "0.1 uF")
      (footprint "eagle-import:R0603")
      (libsource (lib "eagle-import") (part "CAP0603"))
    )
    (comp (ref "C27")
      (value "0.1 uF")
      (footprint "eagle-import:R0603")
      (libsource (lib "eagle-import") (part "CAP0603"))
    )
    (comp (ref "D7")
      (value "S1A")
      (footprint "eagle-import:DO214AC")
      (libsource (lib "eagle-import") (part "DIODE"))
    )
    (comp (ref "D8")
      (value "S1A")
      (footprint "eagle-import:DO214AC")
      (libsource (lib "eagle-import") (part "DIODE"))
    )
    (comp (ref "D9")
      (value "S1A")
      (footprint "eagle-import:DO214AC")
      (libsource (lib "eagle-import") (part "DIODE"))
    )
    (comp (ref "D10")
      (value "S1A")
      (footprint "eagle-import:DO214AC")
      (libsource (lib "eagle-import") (part "DIODE"))
    )
    (comp (ref "Q4")
      (value "IRLML6346TR")
      (footprint "eagle-import:SOT23")
      (libsource (lib "eagle-import") (part "NMOS-FETSOT23"))
    )
    (comp (ref "Q5")
      (value "IRLML6346TR")
      (footprint "eagle-import:SOT23")
      (libsource (lib "eagle-import") (part "NMOS-FETSOT23"))
    )
    (comp (ref "Q6")
      (value "IRLML6346TR")
      (footprint "eagle-import:SOT23")
      (libsource (lib "eagle-import") (part "NMOS-FETSOT23"))
    )
    (comp (ref "Q7")
      (value "IRLML6346TR")
      (footprint "eagle-import:SOT23")
      (libsource (lib "eagle-import") (part "NMOS-FETSOT23"))
    )
    (comp (ref "R24")
      (value "DNP")
      (footprint "eagle-import:R0603")
      (libsource (lib "eagle-import") (part "RESISTOR-0603"))
    )
    (comp (ref "R25")
      (value "DNP")
      (footprint "eagle-import:R0603")
      (libsource (lib "eagle-import") (part "RESISTOR-0603"))
    )
    (comp (ref "R26")
      (value "0 (Jumper)")
      (footprint "eagle-import:R0603")
      (libsource (lib "eagle-import") (part "RESISTOR-0603"))
    )
    (comp (ref "R27")
      (value "DNP")
      (footprint "eagle-import:R0603")
      (libsource (lib "eagle-import") (part "RESISTOR-0603"))
    )
    (comp (ref "R28")
      (value "0 (Jumper)")
      (footprint "eagle-import:R0603")
      (libsource (lib "eagle-import") (part "RESISTOR-0603"))
    )
    (comp (ref "R29")
      (value "DNP")
      (footprint "eagle-import:R0603")
      (libsource (lib "eagle-import") (part "RESISTOR-0603"))
    )
    (comp (ref "R30")
      (value "DNP")
      (footprint "eagle-import:R0603")
      (libsource (lib "eagle-import") (part "RESISTOR-0603"))
    )
    (comp (ref "R31")
      (value "DNP")
      (footprint "eagle-import:R0603")
      (libsource (lib "eagle-import") (part "RESISTOR-0603"))
    )
    (comp (ref "R32")
      (value "DNP")
      (footprint "eagle-import:R0603")
      (libsource (lib "eagle-import") (part "RESISTOR-0603"))
    )
    (comp (ref "R33")
      (value "DNP")
      (footprint "eagle-import:R0603")
      (libsource (lib "eagle-import") (part "RESISTOR-0603"))
    )
    (comp (ref "R34")
      (value "DNP")
      (footprint "eagle-import:R0603")
      (libsource (lib "eagle-import") (part "RESISTOR-0603"))
    )
    (comp (ref "R35")
      (value "DNP")
      (footprint "eagle-import:R0603")
      (libsource (lib "eagle-import") (part "RESISTOR-0603"))
    )
    (comp (ref "R36")
      (value "1K")
      (footprint "eagle-import:R0603")
      (libsource (lib "eagle-import") (part "RESISTOR-0603"))
    )
    (comp (ref "R37")
      (value "1K")
      (footprint "eagle-import:R0603")
      (libsource (lib "eagle-import") (part "RESISTOR-0603"))
    )
    (comp (ref "R38")
      (value "1K")
      (footprint "eagle-import:R0603")
      (libsource (lib "eagle-import") (part "RESISTOR-0603"))
    )
    (comp (ref "R39")
      (value "1K")
      (footprint "eagle-import:R0603")
      (libsource (lib "eagle-import") (part "RESISTOR-0603"))
    )
    (comp (ref "R40")
      (value "10K")
      (footprint "eagle-import:R0603")
      (libsource (lib "eagle-import") (part "RESISTOR-0603"))
    )
    (comp (ref "R41")
      (value "10K")
      (footprint "eagle-import:R0603")
      (libsource (lib "eagle-import") (part "RESISTOR-0603"))
    )
    (comp (ref "R42")
      (value "10K")
      (footprint "eagle-import:R0603")
      (libsource (lib "eagle-import") (part "RESISTOR-0603"))
    )
    (comp (ref "R43")
      (value "10K")
      (footprint "eagle-import:R0603")
      (libsource (lib "eagle-import") (part "RESISTOR-0603"))
    )
    (comp (ref "R44")
      (value "10K")
      (footprint "eagle-import:R0603")
      (libsource (lib "eagle-import") (part "RESISTOR-0603"))
    )
    (comp (ref "R45")
      (value "10K")
      (footprint "eagle-import:R0603")
      (libsource (lib "eagle-import") (part "RESISTOR-0603"))
    )
    (comp (ref "SENS1")
      (value "HIH-5031")
      (footprint "eagle-import:HIH-5031")
      (libsource (lib "eagle-import") (part "HIH-5031"))
    )
    (comp (ref "SENS2")
      (value "MCP9701A")
      (footprint "eagle-import:SOT23")
      (libsource (lib "eagle-import") (part "MCP9701"))
    )
  )
  (nets
    (net (code "1") (name "+3V3") (class "Default")
      (node (ref "C16") (pin "1") (pinfunction "1_1") (pintype "passive"))
      (node (ref "J1") (pin "9") (pinfunction "1_9") (pintype "passive"))
      (node (ref "J18") (pin "5") (pinfunction "1_5") (pintype "passive"))
      (node (ref "J18") (pin "6") (pinfunction "1_6") (pintype "passive"))
      (node (ref "J4") (pin "13") (pinfunction "1_13") (pintype "passive"))
      (node (ref "J5") (pin "14") (pinfunction "14_14") (pintype "passive"))
      (node (ref "J9") (pin "2") (pinfunction "S_2") (pintype "passive"))
      (node (ref "LED8") (pin "A") (pinfunction "A_A") (pintype "passive"))
      (node (ref "Q8") (pin "1") (pinfunction "G_1") (pintype "passive"))
      (node (ref "Q9") (pin "1") (pinfunction "G_1") (pintype "passive"))
      (node (ref "R24") (pin "1") (pinfunction "1_1") (pintype "passive"))
      (node (ref "R27") (pin "1") (pinfunction "1_1") (pintype "passive"))
      (node (ref "R30") (pin "1") (pinfunction "1_1") (pintype "passive"))
      (node (ref "R33") (pin "1") (pinfunction "1_1") (pintype "passive"))
      (node (ref "R57") (pin "2") (pinfunction "2_2") (pintype "passive"))
      (node (ref "R58") (pin "2") (pinfunction "2_2") (pintype "passive"))
      (node (ref "U5") (pin "2") (pinfunction "VOUT_2") (pintype "bidirectional"))
      (node (ref "U5") (pin "4") (pinfunction "VOUT_4") (pintype "bidirectional"))
    )
    (net (code "2") (name "+5V") (class "Default")
      (node (ref "C13") (pin "1") (pinfunction "1_1") (pintype "passive"))
      (node (ref "C14") (pin "1") (pinfunction "1_1") (pintype "passive"))
      (node (ref "C15") (pin "1") (pinfunction "1_1") (pintype "passive"))
      (node (ref "C17") (pin "1") (pinfunction "1_1") (pintype "passive"))
      (node (ref "C18") (pin "1") (pinfunction "1_1") (pintype "passive"))
      (node (ref "C22") (pin "1") (pinfunction "1_1") (pintype "passive"))
      (node (ref "C23") (pin "1") (pinfunction "1_1") (pintype "passive"))
      (node (ref "C24") (pin "1") (pinfunction "1_1") (pintype "passive"))
      (node (ref "C25") (pin "1") (pinfunction "1_1") (pintype "passive"))
      (node (ref "C3") (pin "1") (pinfunction "1_1") (pintype "passive"))
      (node (ref "C30") (pin "1") (pinfunction "1_1") (pintype "passive"))
      (node (ref "C31") (pin "1") (pinfunction "1_1") (pintype "passive"))
      (node (ref "C32") (pin "1") (pinfunction "1_1") (pintype "passive"))
      (node (ref "C33") (pin "1") (pinfunction "1_1") (pintype "passive"))
      (node (ref "C34") (pin "+") (pinfunction "+_+") (pintype "passive"))
      (node (ref "C4") (pin "1") (pinfunction "1_1") (pintype "passive"))
      (node (ref "C7") (pin "1") (pinfunction "1_1") (pintype "passive"))
      (node (ref "J1") (pin "10") (pinfunction "1_10") (pintype "passive"))
      (node (ref "J13") (pin "2") (pinfunction "2_2") (pintype "passive"))
      (node (ref "J2") (pin "1") (pinfunction "1_1") (pintype "passive"))
      (node (ref "J2") (pin "15") (pinfunction "1_15") (pintype "passive"))
      (node (ref "J3") (pin "1") (pinfunction "1_1") (pintype "passive"))
      (node (ref "J3") (pin "15") (pinfunction "1_15") (pintype "passive"))
      (node (ref "J4") (pin "15") (pinfunction "1_15") (pintype "passive"))
      (node (ref "J6") (pin "5") (pinfunction "1_5") (pintype "passive"))
      (node (ref "J6") (pin "6") (pinfunction "1_6") (pintype "passive"))
      (node (ref "L1") (pin "P$2") (pinfunction "2_P$2") (pintype "passive"))
      (node (ref "LED4") (pin "A") (pinfunction "A_A") (pintype "passive"))
      (node (ref "R13") (pin "2") (pinfunction "2_2") (pintype "passive"))
      (node (ref "R16") (pin "2") (pinfunction "2_2") (pintype "passive"))
      (node (ref "R18") (pin "1") (pinfunction "1_1") (pintype "passive"))
      (node (ref "R20") (pin "1") (pinfunction "1_1") (pintype "passive"))
      (node (ref "R25") (pin "1") (pinfunction "1_1") (pintype "passive"))
      (node (ref "R28") (pin "1") (pinfunction "1_1") (pintype "passive"))
      (node (ref "R31") (pin "1") (pinfunction "1_1") (pintype "passive"))
      (node (ref "R34") (pin "1") (pinfunction "1_1") (pintype "passive"))
      (node (ref "R55") (pin "2") (pinfunction "2_2") (pintype "passive"))
      (node (ref "R56") (pin "2") (pinfunction "2_2") (pintype "passive"))
      (node (ref "SENS1") (pin "3") (pinfunction "V+_3") (pintype "bidirectional"))
      (node (ref "SENS2") (pin "1") (pinfunction "VDD_1") (pintype "bidirectional"))
      (node (ref "U1") (pin "3") (pinfunction "V+_3") (pintype "input"))
      (node (ref "U10") (pin "3") (pinfunction "V+_3") (pintype "input"))
      (node (ref "U11") (pin "3") (pinfunction "V+_3") (pintype "input"))
      (node (ref "U2") (pin "3") (pinfunction "V+_3") (pintype "input"))
      (node (ref "U3") (pin "3") (pinfunction "V+_3") (pintype "input"))
      (node (ref "U5") (pin "3") (pinfunction "VIN_3") (pintype "input"))
      (node (ref "U6") (pin "10") (pinfunction "VCC_10") (pintype "input"))
      (node (ref "U6") (pin "100") (pinfunction "AVCC_100") (pintype "input"))
      (node (ref "U6") (pin "31") (pinfunction "VCC1_31") (pintype "input"))
      (node (ref "U6") (pin "61") (pinfunction "VCC2_61") (pintype "input"))
      (node (ref "U6") (pin "80") (pinfunction "VCC3_80") (pintype "input"))
      (node (ref "U7") (pin "19") (pinfunction "VCCB_19") (pintype "bidirectional"))
      (node (ref "U9") (pin "3") (pinfunction "V+_3") (pintype "input"))
    )
    (net (code "3") (name "3V3_SCL") (class "Default")
      (node (ref "J1") (pin "11") (pinfunction "1_11") (pintype "passive"))
      (node (ref "J5") (pin "15") (pinfunction "15_15") (pintype "passive"))
      (node (ref "Q8") (pin "2") (pinfunction "S_2") (pintype "passive"))
      (node (ref "R57") (pin "1") (pinfunction "1_1") (pintype "passive"))
    )
    (net (code "4") (name "3V3_SDA") (class "Default")
      (node (ref "J1") (pin "13") (pinfunction "1_13") (pintype "passive"))
      (node (ref "J5") (pin "16") (pinfunction "16_16") (pintype "passive"))
      (node (ref "Q9") (pin "2") (pinfunction "S_2") (pintype "passive"))
      (node (ref "R58") (pin "1") (pinfunction "1_1") (pintype "passive"))
    )
    (net (code "5") (name "ADC0") (class "Default")
      (node (ref "U3") (pin "6") (pinfunction "VOUT_6") (pintype "output"))
      (node (ref "U6") (pin "97") (pinfunction "(ADC0)PF0_97") (pintype "bidirectional"))
    )
    (net (code "6") (name "ADC1") (class "Default")
      (node (ref "C38") (pin "1") (pinfunction "1_1") (pintype "passive"))
      (node (ref "R66") (pin "2") (pinfunction "2_2") (pintype "passive"))
      (node (ref "U6") (pin "96") (pinfunction "(ADC1)PF1_96") (pintype "bidirectional"))
    )
    (net (code "7") (name "ADC2") (class "Default")
      (node (ref "C37") (pin "1") (pinfunction "1_1") (pintype "passive"))
      (node (ref "R50") (pin "2") (pinfunction "2_2") (pintype "passive"))
      (node (ref "U6") (pin "95") (pinfunction "(ADC2)PF2_95") (pintype "bidirectional"))
    )
    (net (code "8") (name "ADC3") (class "Default")
      (node (ref "C36") (pin "1") (pinfunction "1_1") (pintype "passive"))
      (node (ref "R49") (pin "2") (pinfunction "2_2") (pintype "passive"))
      (node (ref "U6") (pin "94") (pinfunction "(ADC3)PF3_94") (pintype "bidirectional"))
    )
    (net (code "9") (name "ADC4") (class "Default")
      (node (ref "C6") (pin "1") (pinfunction "1_1") (pintype "passive"))
      (node (ref "R10") (pin "2") (pinfunction "2_2") (pintype "passive"))
      (node (ref "R11") (pin "1") (pinfunction "1_1") (pintype "passive"))
      (node (ref "U6") (pin "93") (pinfunction "(ADC4/TCK)PF4_93") (pintype "bidirectional"))
    )
    (net (code "10") (name "ADC5") (class "Default")
      (node (ref "U1") (pin "6") (pinfunction "VOUT_6") (pintype "output"))
      (node (ref "U6") (pin "92") (pinfunction "(ADC5/TMS)PF5_92") (pintype "bidirectional"))
    )
    (net (code "11") (name "ADC6") (class "Default")
      (node (ref "U2") (pin "6") (pinfunction "VOUT_6") (pintype "output"))
      (node (ref "U6") (pin "91") (pinfunction "(ADC6/TDO)PF6_91") (pintype "bidirectional"))
    )
    (net (code "12") (name "ADC7") (class "Default")
      (node (ref "C27") (pin "1") (pinfunction "1_1") (pintype "passive"))
      (node (ref "R45") (pin "2") (pinfunction "2_2") (pintype "passive"))
      (node (ref "U6") (pin "90") (pinfunction "(ADC7/TDI)PF7_90") (pintype "bidirectional"))
    )
    (net (code "13") (name "ADC8") (class "Default")
      (node (ref "C26") (pin "1") (pinfunction "1_1") (pintype "passive"))
      (node (ref "R44") (pin "2") (pinfunction "2_2") (pintype "passive"))
      (node (ref "U6") (pin "89") (pinfunction "PK0(ADC8/PCINT16)_89") (pintype "bidirectional"))
    )
    (net (code "14") (name "ADC9") (class "Default")
      (node (ref "J4") (pin "14") (pinfunction "1_14") (pintype "passive"))
      (node (ref "U6") (pin "88") (pinfunction "PK1(ADC9/PCINT17)_88") (pintype "bidirectional"))
    )
    (net (code "15") (name "ADC10") (class "Default")
      (node (ref "J4") (pin "12") (pinfunction "1_12") (pintype "passive"))
      (node (ref "U6") (pin "87") (pinfunction "PK2(ADC10/PCINT18)_87") (pintype "bidirectional"))
    )
    (net (code "16") (name "ADC11") (class "Default")
      (node (ref "J4") (pin "10") (pinfunction "1_10") (pintype "passive"))
      (node (ref "U6") (pin "86") (pinfunction "PK3(ADC11/PCINT19)_86") (pintype "bidirectional"))
    )
    (net (code "17") (name "ADC12") (class "Default")
      (node (ref "J4") (pin "8") (pinfunction "1_8") (pintype "passive"))
      (node (ref "U6") (pin "85") (pinfunction "PK4(ADC12/PCINT20)_85") (pintype "bidirectional"))
    )
    (net (code "18") (name "ADC13") (class "Default")
      (node (ref "J4") (pin "6") (pinfunction "1_6") (pintype "passive"))
      (node (ref "U6") (pin "84") (pinfunction "PK5(ADC13/PCINT21)_84") (pintype "bidirectional"))
    )
    (net (code "19") (name "ADC14") (class "Default")
      (node (ref "J4") (pin "4") (pinfunction "1_4") (pintype "passive"))
      (node (ref "U6") (pin "83") (pinfunction "PK6(ADC14/PCINT22)_83") (pintype "bidirectional"))
    )
    (net (code "20") (name "ADC15") (class "Default")
      (node (ref "J4") (pin "2") (pinfunction "1_2") (pintype "passive"))
      (node (ref "U6") (pin "82") (pinfunction "PK7(ADC15/PCINT23)_82") (pintype "bidirectional"))
    )
    (net (code "21") (name "AREF") (class "Default")
      (node (ref "C21") (pin "1") (pinfunction "1_1") (pintype "passive"))
      (node (ref "J4") (pin "16") (pinfunction "1_16") (pintype "passive"))
      (node (ref "U6") (pin "98") (pinfunction "AREF_98") (pintype "bidirectional"))
    )
    (net (code "22") (name "BAT_1+") (class "Default")
      (node (ref "C1") (pin "1") (pinfunction "1_1") (pintype "passive"))
      (node (ref "D1") (pin "1") (pinfunction "A_1") (pintype "passive"))
      (node (ref "D1") (pin "3") (pinfunction "A_3") (pintype "passive"))
      (node (ref "J5") (pin "5") (pinfunction "5_5") (pintype "passive"))
    )
    (net (code "23") (name "BAT_2+") (class "Default")
      (node (ref "C2") (pin "1") (pinfunction "1_1") (pintype "passive"))
      (node (ref "D2") (pin "1") (pinfunction "A_1") (pintype "passive"))
      (node (ref "D2") (pin "3") (pinfunction "A_3") (pintype "passive"))
      (node (ref "J5") (pin "6") (pinfunction "6_6") (pintype "passive"))
    )
    (net (code "24") (name "BB_3V3") (class "Default")
      (node (ref "C28") (pin "1") (pinfunction "1_1") (pintype "passive"))
      (node (ref "C29") (pin "1") (pinfunction "1_1") (pintype "passive"))
      (node (ref "J6") (pin "3") (pinfunction "1_3") (pintype "passive"))
      (node (ref "J6") (pin "4") (pinfunction "1_4") (pintype "passive"))
      (node (ref "LED3") (pin "A") (pinfunction "A_A") (pintype "passive"))
      (node (ref "R46") (pin "2") (pinfunction "2_2") (pintype "passive"))
      (node (ref "R47") (pin "2") (pinfunction "2_2") (pintype "passive"))
      (node (ref "R51") (pin "2") (pinfunction "2_2") (pintype "passive"))
      (node (ref "R52") (pin "2") (pinfunction "2_2") (pintype "passive"))
      (node (ref "R53") (pin "2") (pinfunction "2_2") (pintype "passive"))
      (node (ref "R54") (pin "2") (pinfunction "2_2") (pintype "passive"))
      (node (ref "R62") (pin "2") (pinfunction "2_2") (pintype "passive"))
      (node (ref "U7") (pin "2") (pinfunction "VCCA_2") (pintype "bidirectional"))
      (node (ref "U8") (pin "8") (pinfunction "VCC_8") (pintype "bidirectional"))
    )
    (net (code "25") (name "BB_P9_11") (class "Default")
      (node (ref "J6") (pin "11") (pinfunction "1_11") (pintype "passive"))
      (node (ref "R46") (pin "1") (pinfunction "1_1") (pintype "passive"))
      (node (ref "U7") (pin "8") (pinfunction "A7_8") (pintype "bidirectional"))
    )
    (net (code "26") (name "BB_P9_12") (class "Default")
      (node (ref "J6") (pin "12") (pinfunction "1_12") (pintype "passive"))
    )
    (net (code "27") (name "BB_P9_13") (class "Default")
      (node (ref "J6") (pin "13") (pinfunction "1_13") (pintype "passive"))
    )
    (net (code "28") (name "BB_P9_14") (class "Default")
      (node (ref "J6") (pin "14") (pinfunction "1_14") (pintype "passive"))
    )
    (net (code "29") (name "BB_P9_15") (class "Default")
      (node (ref "J6") (pin "15") (pinfunction "1_15") (pintype "passive"))
    )
    (net (code "30") (name "BB_P9_16") (class "Default")
      (node (ref "J6") (pin "16") (pinfunction "1_16") (pintype "passive"))
    )
    (net (code "31") (name "BB_P9_17") (class "Default")
      (node (ref "J6") (pin "17") (pinfunction "1_17") (pintype "passive"))
      (node (ref "U7") (pin "4") (pinfunction "A3_4") (pintype "bidirectional"))
    )
    (net (code "32") (name "BB_P9_18") (class "Default")
      (node (ref "J6") (pin "18") (pinfunction "1_18") (pintype "passive"))
      (node (ref "U7") (pin "6") (pinfunction "A5_6") (pintype "bidirectional"))
    )
    (net (code "33") (name "BB_P9_19") (class "Default")
      (node (ref "J6") (pin "19") (pinfunction "1_19") (pintype "passive"))
      (node (ref "R53") (pin "1") (pinfunction "1_1") (pintype "passive"))
      (node (ref "U8") (pin "6") (pinfunction "SCL_6") (pintype "bidirectional"))
    )
    (net (code "34") (name "BB_P9_20") (class "Default")
      (node (ref "J6") (pin "20") (pinfunction "1_20") (pintype "passive"))
      (node (ref "R54") (pin "1") (pinfunction "1_1") (pintype "passive"))
      (node (ref "U8") (pin "5") (pinfunction "SDA_5") (pintype "bidirectional"))
    )
    (net (code "35") (name "BB_P9_21") (class "Default")
      (node (ref "J6") (pin "21") (pinfunction "1_21") (pintype "passive"))
      (node (ref "U7") (pin "7") (pinfunction "A6_7") (pintype "bidirectional"))
    )
    (net (code "36") (name "BB_P9_22") (class "Default")
      (node (ref "J6") (pin "22") (pinfunction "1_22") (pintype "passive"))
      (node (ref "U7") (pin "5") (pinfunction "A4_5") (pintype "bidirectional"))
    )
    (net (code "37") (name "BB_P9_23") (class "Default")
      (node (ref "J6") (pin "23") (pinfunction "1_23") (pintype "passive"))
    )
    (net (code "38") (name "BB_P9_24") (class "Default")
      (node (ref "J6") (pin "24") (pinfunction "1_24") (pintype "passive"))
      (node (ref "R21") (pin "2") (pinfunction "2_2") (pintype "passive"))
      (node (ref "U7") (pin "1") (pinfunction "A1_1") (pintype "bidirectional"))
    )
    (net (code "39") (name "BB_P9_25") (class "Default")
      (node (ref "J6") (pin "25") (pinfunction "1_25") (pintype "passive"))
    )
    (net (code "40") (name "BB_P9_26") (class "Default")
      (node (ref "J6") (pin "26") (pinfunction "1_26") (pintype "passive"))
      (node (ref "U7") (pin "3") (pinfunction "A2_3") (pintype "bidirectional"))
    )
    (net (code "41") (name "BB_P9_27") (class "Default")
      (node (ref "J6") (pin "27") (pinfunction "1_27") (pintype "passive"))
    )
    (net (code "42") (name "BB_P9_28") (class "Default")
      (node (ref "J6") (pin "28") (pinfunction "1_28") (pintype "passive"))
    )
    (net (code "43") (name "BB_P9_29") (class "Default")
      (node (ref "J6") (pin "29") (pinfunction "1_29") (pintype "passive"))
    )
    (net (code "44") (name "BB_P9_30") (class "Default")
      (node (ref "J6") (pin "30") (pinfunction "1_30") (pintype "passive"))
    )
    (net (code "45") (name "BB_P9_31") (class "Default")
      (node (ref "J6") (pin "31") (pinfunction "1_31") (pintype "passive"))
    )
    (net (code "46") (name "BB_P9_32") (class "Default")
      (node (ref "J6") (pin "32") (pinfunction "1_32") (pintype "passive"))
    )
    (net (code "47") (name "BB_P9_33") (class "Default")
      (node (ref "J6") (pin "33") (pinfunction "1_33") (pintype "passive"))
    )
    (net (code "48") (name "BB_P9_34") (class "Default")
      (node (ref "J6") (pin "34") (pinfunction "1_34") (pintype "passive"))
    )
    (net (code "49") (name "BB_P9_35") (class "Default")
      (node (ref "J6") (pin "35") (pinfunction "1_35") (pintype "passive"))
    )
    (net (code "50") (name "BB_P9_36") (class "Default")
      (node (ref "J6") (pin "36") (pinfunction "1_36") (pintype "passive"))
    )
    (net (code "51") (name "BB_P9_37") (class "Default")
      (node (ref "J6") (pin "37") (pinfunction "1_37") (pintype "passive"))
    )
    (net (code "52") (name "BB_P9_38") (class "Default")
      (node (ref "J6") (pin "38") (pinfunction "1_38") (pintype "passive"))
    )
    (net (code "53") (name "BB_P9_39") (class "Default")
      (node (ref "J6") (pin "39") (pinfunction "1_39") (pintype "passive"))
    )
    (net (code "54") (name "BB_P9_40") (class "Default")
      (node (ref "J6") (pin "40") (pinfunction "1_40") (pintype "passive"))
    )
    (net (code "55") (name "BB_P9_41") (class "Default")
      (node (ref "J6") (pin "41") (pinfunction "1_41") (pintype "passive"))
    )
    (net (code "56") (name "BB_P9_42") (class "Default")
      (node (ref "J6") (pin "42") (pinfunction "1_42") (pintype "passive"))
    )
    (net (code "57") (name "BB_PWR_BUT") (class "Default")
      (node (ref "J6") (pin "9") (pinfunction "1_9") (pintype "passive"))
    )
    (net (code "58") (name "BB_SYS_5V") (class "Default")
      (node (ref "J6") (pin "7") (pinfunction "1_7") (pintype "passive"))
      (node (ref "J6") (pin "8") (pinfunction "1_8") (pintype "passive"))
    )
    (net (code "59") (name "BB_SYS_RESET*") (class "Default")
      (node (ref "J6") (pin "10") (pinfunction "1_10") (pintype "passive"))
      (node (ref "R48") (pin "2") (pinfunction "2_2") (pintype "passive"))
    )
    (net (code "60") (name "D0{slash}UART_RX") (class "Default")
      (node (ref "U6") (pin "2") (pinfunction "(RXD0/PCIN8)PE0_2") (pintype "bidirectional"))
      (node (ref "U7") (pin "20") (pinfunction "B1_20") (pintype "bidirectional"))
    )
    (net (code "61") (name "D1{slash}UART_TX") (class "Default")
      (node (ref "R22") (pin "2") (pinfunction "2_2") (pintype "passive"))
      (node (ref "U6") (pin "3") (pinfunction "(TXD0)PE1_3") (pintype "bidirectional"))
      (node (ref "U7") (pin "18") (pinfunction "B2_18") (pintype "bidirectional"))
    )
    (net (code "62") (name "D2") (class "Default")
      (node (ref "J3") (pin "11") (pinfunction "1_11") (pintype "passive"))
      (node (ref "U6") (pin "6") (pinfunction "(OC3B/INT4)PE4_6") (pintype "bidirectional"))
    )
    (net (code "63") (name "D3") (class "Default")
      (node (ref "J3") (pin "9") (pinfunction "1_9") (pintype "passive"))
      (node (ref "U6") (pin "7") (pinfunction "(OC3C/INT5)PE5_7") (pintype "bidirectional"))
    )
    (net (code "64") (name "D4") (class "Default")
      (node (ref "J3") (pin "7") (pinfunction "1_7") (pintype "passive"))
      (node (ref "U6") (pin "1") (pinfunction "(OC0B)PG5_1") (pintype "bidirectional"))
    )
    (net (code "65") (name "D5") (class "Default")
      (node (ref "J3") (pin "5") (pinfunction "1_5") (pintype "passive"))
      (node (ref "U6") (pin "5") (pinfunction "(OC3A/AIN1)PE3_5") (pintype "bidirectional"))
    )
    (net (code "66") (name "D6") (class "Default")
      (node (ref "J20") (pin "P1") (pinfunction "1_P1") (pintype "passive"))
      (node (ref "U6") (pin "15") (pinfunction "PH3(OC4A)_15") (pintype "bidirectional"))
    )
    (net (code "67") (name "D7") (class "Default")
      (node (ref "J20") (pin "P4") (pinfunction "1_P4") (pintype "passive"))
      (node (ref "U6") (pin "16") (pinfunction "PH4(OC4B)_16") (pintype "bidirectional"))
    )
    (net (code "68") (name "D8") (class "Default")
      (node (ref "J20") (pin "P7") (pinfunction "1_P7") (pintype "passive"))
      (node (ref "U6") (pin "17") (pinfunction "PH5(OC4C)_17") (pintype "bidirectional"))
    )
    (net (code "69") (name "D9") (class "Default")
      (node (ref "J21") (pin "P1") (pinfunction "1_P1") (pintype "passive"))
      (node (ref "U6") (pin "18") (pinfunction "PH6(OC2B)_18") (pintype "bidirectional"))
    )
    (net (code "70") (name "D10") (class "Default")
      (node (ref "J21") (pin "P4") (pinfunction "1_P4") (pintype "passive"))
      (node (ref "U6") (pin "23") (pinfunction "(OC2A/PCINT4)PB4_23") (pintype "bidirectional"))
    )
    (net (code "71") (name "D11") (class "Default")
      (node (ref "J21") (pin "P7") (pinfunction "1_P7") (pintype "passive"))
      (node (ref "U6") (pin "24") (pinfunction "(OC1A/PCINT5)PB5_24") (pintype "bidirectional"))
    )
    (net (code "72") (name "D12") (class "Default")
      (node (ref "R39") (pin "1") (pinfunction "1_1") (pintype "passive"))
      (node (ref "U6") (pin "25") (pinfunction "(OC1B/PCINT6)PB6_25") (pintype "bidirectional"))
    )
    (net (code "73") (name "D13") (class "Default")
      (node (ref "R23") (pin "1") (pinfunction "1_1") (pintype "passive"))
      (node (ref "U6") (pin "26") (pinfunction "(OC0A/OC1C/PCINT7)PB7_26") (pintype "bidirectional"))
    )
    (net (code "74") (name "D14") (class "Default")
      (node (ref "J2") (pin "11") (pinfunction "1_11") (pintype "passive"))
      (node (ref "U6") (pin "64") (pinfunction "PJ1(TXD3/PCINT10)_64") (pintype "bidirectional"))
    )
    (net (code "75") (name "D15") (class "Default")
      (node (ref "J2") (pin "9") (pinfunction "1_9") (pintype "passive"))
      (node (ref "U6") (pin "63") (pinfunction "PJ0(RXD3/PCINT9)_63") (pintype "bidirectional"))
    )
    (net (code "76") (name "D16{slash}ESC_POWER_SWITCH") (class "Default")
      (node (ref "R5") (pin "2") (pinfunction "2_2") (pintype "passive"))
      (node (ref "U6") (pin "13") (pinfunction "PH1(TXD2)_13") (pintype "bidirectional"))
    )
    (net (code "77") (name "D17") (class "Default")
      (node (ref "U6") (pin "12") (pinfunction "PH0(RXD2)_12") (pintype "bidirectional"))
    )
    (net (code "78") (name "D18") (class "Default")
      (node (ref "J2") (pin "7") (pinfunction "1_7") (pintype "passive"))
      (node (ref "U6") (pin "46") (pinfunction "(TXD1/INT3)PD3_46") (pintype "bidirectional"))
    )
    (net (code "79") (name "D19") (class "Default")
      (node (ref "J2") (pin "5") (pinfunction "1_5") (pintype "passive"))
      (node (ref "U6") (pin "45") (pinfunction "(RXD1/INT2)PD2_45") (pintype "bidirectional"))
    )
    (net (code "80") (name "D20{slash}5V_SDA") (class "Default")
      (node (ref "J1") (pin "14") (pinfunction "1_14") (pintype "passive"))
      (node (ref "Q9") (pin "3") (pinfunction "D_3") (pintype "passive"))
      (node (ref "R56") (pin "1") (pinfunction "1_1") (pintype "passive"))
      (node (ref "U6") (pin "44") (pinfunction "(SDA/INT1)PD1_44") (pintype "bidirectional"))
    )
    (net (code "81") (name "D21{slash}5V_SCL") (class "Default")
      (node (ref "J1") (pin "12") (pinfunction "1_12") (pintype "passive"))
      (node (ref "Q8") (pin "3") (pinfunction "D_3") (pintype "passive"))
      (node (ref "R55") (pin "1") (pinfunction "1_1") (pintype "passive"))
      (node (ref "U6") (pin "43") (pinfunction "(SCL/INT0)PD0_43") (pintype "bidirectional"))
    )
    (net (code "82") (name "D22") (class "Default")
      (node (ref "J3") (pin "16") (pinfunction "1_16") (pintype "passive"))
      (node (ref "U6") (pin "78") (pinfunction "(AD0)PA0_78") (pintype "bidirectional"))
    )
    (net (code "83") (name "D23") (class "Default")
      (node (ref "J3") (pin "14") (pinfunction "1_14") (pintype "passive"))
      (node (ref "U6") (pin "77") (pinfunction "(AD1)PA1_77") (pintype "bidirectional"))
    )
    (net (code "84") (name "D24") (class "Default")
      (node (ref "J3") (pin "12") (pinfunction "1_12") (pintype "passive"))
      (node (ref "U6") (pin "76") (pinfunction "(AD2)PA2_76") (pintype "bidirectional"))
    )
    (net (code "85") (name "D25") (class "Default")
      (node (ref "J3") (pin "10") (pinfunction "1_10") (pintype "passive"))
      (node (ref "U6") (pin "75") (pinfunction "(AD3)PA3_75") (pintype "bidirectional"))
    )
    (net (code "86") (name "D26") (class "Default")
      (node (ref "J3") (pin "8") (pinfunction "1_8") (pintype "passive"))
      (node (ref "U6") (pin "74") (pinfunction "(AD4)PA4_74") (pintype "bidirectional"))
    )
    (net (code "87") (name "D27") (class "Default")
      (node (ref "J3") (pin "6") (pinfunction "1_6") (pintype "passive"))
      (node (ref "U6") (pin "73") (pinfunction "(AD5)PA5_73") (pintype "bidirectional"))
    )
    (net (code "88") (name "D28") (class "Default")
      (node (ref "J3") (pin "4") (pinfunction "1_4") (pintype "passive"))
      (node (ref "U6") (pin "72") (pinfunction "(AD6)PA6_72") (pintype "bidirectional"))
    )
    (net (code "89") (name "D29") (class "Default")
      (node (ref "J3") (pin "2") (pinfunction "1_2") (pintype "passive"))
      (node (ref "U6") (pin "71") (pinfunction "(AD7)PA7_71") (pintype "bidirectional"))
    )
    (net (code "90") (name "D30") (class "Default")
      (node (ref "J2") (pin "16") (pinfunction "1_16") (pintype "passive"))
      (node (ref "U6") (pin "60") (pinfunction "(A15)PC7_60") (pintype "bidirectional"))
    )
    (net (code "91") (name "D31") (class "Default")
      (node (ref "J2") (pin "14") (pinfunction "1_14") (pintype "passive"))
      (node (ref "U6") (pin "59") (pinfunction "(A14)PC6_59") (pintype "bidirectional"))
    )
    (net (code "92") (name "D32") (class "Default")
      (node (ref "J2") (pin "12") (pinfunction "1_12") (pintype "passive"))
      (node (ref "U6") (pin "58") (pinfunction "(A13)PC5_58") (pintype "bidirectional"))
    )
    (net (code "93") (name "D33") (class "Default")
      (node (ref "J2") (pin "10") (pinfunction "1_10") (pintype "passive"))
      (node (ref "U6") (pin "57") (pinfunction "(A12)PC4_57") (pintype "bidirectional"))
    )
    (net (code "94") (name "D34") (class "Default")
      (node (ref "J2") (pin "8") (pinfunction "1_8") (pintype "passive"))
      (node (ref "U6") (pin "56") (pinfunction "(A11)PC3_56") (pintype "bidirectional"))
    )
    (net (code "95") (name "D35") (class "Default")
      (node (ref "J2") (pin "6") (pinfunction "1_6") (pintype "passive"))
      (node (ref "U6") (pin "55") (pinfunction "(A10)PC2_55") (pintype "bidirectional"))
    )
    (net (code "96") (name "D36") (class "Default")
      (node (ref "J2") (pin "4") (pinfunction "1_4") (pintype "passive"))
      (node (ref "U6") (pin "54") (pinfunction "(A9)PC1_54") (pintype "bidirectional"))
    )
    (net (code "97") (name "D37") (class "Default")
      (node (ref "J2") (pin "2") (pinfunction "1_2") (pintype "passive"))
      (node (ref "U6") (pin "53") (pinfunction "(A8)PC0_53") (pintype "bidirectional"))
    )
    (net (code "98") (name "D38") (class "Default")
      (node (ref "U6") (pin "50") (pinfunction "(T0)PD7_50") (pintype "bidirectional"))
    )
    (net (code "99") (name "D39") (class "Default")
      (node (ref "U6") (pin "70") (pinfunction "(ALE)PG2_70") (pintype "bidirectional"))
    )
    (net (code "100") (name "D40") (class "Default")
      (node (ref "U6") (pin "52") (pinfunction "(RD)PG1_52") (pintype "bidirectional"))
    )
    (net (code "101") (name "D41") (class "Default")
      (node (ref "U6") (pin "51") (pinfunction "(WR)PG0_51") (pintype "bidirectional"))
    )
    (net (code "102") (name "D42") (class "Default")
      (node (ref "U6") (pin "42") (pinfunction "PL7_42") (pintype "bidirectional"))
    )
    (net (code "103") (name "D43") (class "Default")
      (node (ref "U6") (pin "41") (pinfunction "PL6_41") (pintype "bidirectional"))
    )
    (net (code "104") (name "D44") (class "Default")
      (node (ref "R36") (pin "1") (pinfunction "1_1") (pintype "passive"))
      (node (ref "U6") (pin "40") (pinfunction "PL5(OC5C)_40") (pintype "bidirectional"))
    )
    (net (code "105") (name "D45") (class "Default")
      (node (ref "R37") (pin "1") (pinfunction "1_1") (pintype "passive"))
      (node (ref "U6") (pin "39") (pinfunction "PL4(OC5B)_39") (pintype "bidirectional"))
    )
    (net (code "106") (name "D46") (class "Default")
      (node (ref "R38") (pin "1") (pinfunction "1_1") (pintype "passive"))
      (node (ref "U6") (pin "38") (pinfunction "PL3(OC5A)_38") (pintype "bidirectional"))
    )
    (net (code "107") (name "D47") (class "Default")
      (node (ref "U6") (pin "37") (pinfunction "PL2(T5)_37") (pintype "bidirectional"))
    )
    (net (code "108") (name "D48") (class "Default")
      (node (ref "U6") (pin "36") (pinfunction "PL1(ICP5)_36") (pintype "bidirectional"))
    )
    (net (code "109") (name "D49") (class "Default")
      (node (ref "R19") (pin "1") (pinfunction "1_1") (pintype "passive"))
      (node (ref "U6") (pin "35") (pinfunction "PL0(ICP4)_35") (pintype "bidirectional"))
    )
    (net (code "110") (name "D50{slash}SPI_MISO") (class "Default")
      (node (ref "J13") (pin "1") (pinfunction "1_1") (pintype "passive"))
      (node (ref "U6") (pin "22") (pinfunction "(MISO/PCINT3)PB3_22") (pintype "bidirectional"))
      (node (ref "U7") (pin "14") (pinfunction "B6_14") (pintype "bidirectional"))
    )
    (net (code "111") (name "D51{slash}SPI_MOSI") (class "Default")
      (node (ref "J13") (pin "4") (pinfunction "4_4") (pintype "passive"))
      (node (ref "U6") (pin "21") (pinfunction "(MOSI/PCINT2)PB2_21") (pintype "bidirectional"))
      (node (ref "U7") (pin "15") (pinfunction "B5_15") (pintype "bidirectional"))
    )
    (net (code "112") (name "D52{slash}SPI_SCK") (class "Default")
      (node (ref "J13") (pin "3") (pinfunction "3_3") (pintype "passive"))
      (node (ref "U6") (pin "20") (pinfunction "(SCK/PCINT1)PB1_20") (pintype "bidirectional"))
      (node (ref "U7") (pin "16") (pinfunction "B4_16") (pintype "bidirectional"))
    )
    (net (code "113") (name "D53{slash}SPI_SS") (class "Default")
      (node (ref "U6") (pin "19") (pinfunction "(SS/PCINT0)PB0_19") (pintype "bidirectional"))
      (node (ref "U7") (pin "17") (pinfunction "B3_17") (pintype "bidirectional"))
    )
    (net (code "114") (name "ESC_1A") (class "Default")
      (node (ref "J14") (pin "2") (pinfunction "S_2") (pintype "passive"))
      (node (ref "J5") (pin "1") (pinfunction "1_1") (pintype "passive"))
    )
    (net (code "115") (name "ESC_1B") (class "Default")
      (node (ref "J14") (pin "3") (pinfunction "S_3") (pintype "passive"))
      (node (ref "J5") (pin "2") (pinfunction "2_2") (pintype "passive"))
    )
    (net (code "116") (name "ESC_1C") (class "Default")
      (node (ref "J14") (pin "4") (pinfunction "S_4") (pintype "passive"))
      (node (ref "J5") (pin "3") (pinfunction "3_3") (pintype "passive"))
    )
    (net (code "117") (name "ESC_2A") (class "Default")
      (node (ref "J15") (pin "2") (pinfunction "S_2") (pintype "passive"))
      (node (ref "J5") (pin "8") (pinfunction "8_8") (pintype "passive"))
    )
    (net (code "118") (name "ESC_2B") (class "Default")
      (node (ref "J15") (pin "3") (pinfunction "S_3") (pintype "passive"))
      (node (ref "J5") (pin "9") (pinfunction "9_9") (pintype "passive"))
    )
    (net (code "119") (name "ESC_2C") (class "Default")
      (node (ref "J15") (pin "4") (pinfunction "S_4") (pintype "passive"))
      (node (ref "J5") (pin "10") (pinfunction "10_10") (pintype "passive"))
    )
    (net (code "120") (name "ESC_3A") (class "Default")
      (node (ref "J16") (pin "2") (pinfunction "S_2") (pintype "passive"))
      (node (ref "J5") (pin "11") (pinfunction "11_11") (pintype "passive"))
    )
    (net (code "121") (name "ESC_3B") (class "Default")
      (node (ref "J16") (pin "3") (pinfunction "S_3") (pintype "passive"))
      (node (ref "J5") (pin "12") (pinfunction "12_12") (pintype "passive"))
    )
    (net (code "122") (name "ESC_3C") (class "Default")
      (node (ref "J16") (pin "4") (pinfunction "S_4") (pintype "passive"))
      (node (ref "J5") (pin "13") (pinfunction "13_13") (pintype "passive"))
    )
    (net (code "123") (name "ESC_POWER") (class "Default")
      (node (ref "Q3") (pin "5") (pinfunction "D_5") (pintype "passive"))
      (node (ref "Q3") (pin "6") (pinfunction "D_6") (pintype "passive"))
      (node (ref "Q3") (pin "7") (pinfunction "D_7") (pintype "passive"))
      (node (ref "Q3") (pin "8") (pinfunction "D_8") (pintype "passive"))
      (node (ref "R59") (pin "1") (pinfunction "1_1") (pintype "passive"))
      (node (ref "R60") (pin "1") (pinfunction "1_1") (pintype "passive"))
      (node (ref "R61") (pin "1") (pinfunction "1_1") (pintype "passive"))
      (node (ref "U10") (pin "4") (pinfunction "IN+_4") (pintype "input"))
      (node (ref "U11") (pin "4") (pinfunction "IN+_4") (pintype "input"))
      (node (ref "U9") (pin "4") (pinfunction "IN+_4") (pintype "input"))
    )
    (net (code "124") (name "GND") (class "Default")
      (node (ref "C1") (pin "2") (pinfunction "2_2") (pintype "passive"))
      (node (ref "C10") (pin "2") (pinfunction "2_2") (pintype "passive"))
      (node (ref "C11") (pin "2") (pinfunction "2_2") (pintype "passive"))
      (node (ref "C13") (pin "2") (pinfunction "2_2") (pintype "passive"))
      (node (ref "C14") (pin "2") (pinfunction "2_2") (pintype "passive"))
      (node (ref "C15") (pin "2") (pinfunction "2_2") (pintype "passive"))
      (node (ref "C16") (pin "2") (pinfunction "2_2") (pintype "passive"))
      (node (ref "C17") (pin "2") (pinfunction "2_2") (pintype "passive"))
      (node (ref "C18") (pin "2") (pinfunction "2_2") (pintype "passive"))
      (node (ref "C19") (pin "2") (pinfunction "2_2") (pintype "passive"))
      (node (ref "C2") (pin "2") (pinfunction "2_2") (pintype "passive"))
      (node (ref "C20") (pin "2") (pinfunction "2_2") (pintype "passive"))
      (node (ref "C21") (pin "2") (pinfunction "2_2") (pintype "passive"))
      (node (ref "C22") (pin "2") (pinfunction "2_2") (pintype "passive"))
      (node (ref "C23") (pin "2") (pinfunction "2_2") (pintype "passive"))
      (node (ref "C24") (pin "2") (pinfunction "2_2") (pintype "passive"))
      (node (ref "C25") (pin "2") (pinfunction "2_2") (pintype "passive"))
      (node (ref "C26") (pin "2") (pinfunction "2_2") (pintype "passive"))
      (node (ref "C27") (pin "2") (pinfunction "2_2") (pintype "passive"))
      (node (ref "C28") (pin "2") (pinfunction "2_2") (pintype "passive"))
      (node (ref "C29") (pin "2") (pinfunction "2_2") (pintype "passive"))
      (node (ref "C3") (pin "2") (pinfunction "2_2") (pintype "passive"))
      (node (ref "C30") (pin "2") (pinfunction "2_2") (pintype "passive"))
      (node (ref "C31") (pin "2") (pinfunction "2_2") (pintype "passive"))
      (node (ref "C32") (pin "2") (pinfunction "2_2") (pintype "passive"))
      (node (ref "C33") (pin "2") (pinfunction "2_2") (pintype "passive"))
      (node (ref "C34") (pin "-") (pinfunction "-_-") (pintype "passive"))
      (node (ref "C35") (pin "2") (pinfunction "2_2") (pintype "passive"))
      (node (ref "C36") (pin "2") (pinfunction "2_2") (pintype "passive"))
      (node (ref "C37") (pin "2") (pinfunction "2_2") (pintype "passive"))
      (node (ref "C38") (pin "2") (pinfunction "2_2") (pintype "passive"))
      (node (ref "C4") (pin "2") (pinfunction "2_2") (pintype "passive"))
      (node (ref "C6") (pin "2") (pinfunction "2_2") (pintype "passive"))
      (node (ref "C7") (pin "2") (pinfunction "2_2") (pintype "passive"))
      (node (ref "C8") (pin "2") (pinfunction "2_2") (pintype "passive"))
      (node (ref "C9") (pin "2") (pinfunction "2_2") (pintype "passive"))
      (node (ref "D3") (pin "A") (pinfunction "A_A") (pintype "passive"))
      (node (ref "J1") (pin "15") (pinfunction "1_15") (pintype "passive"))
      (node (ref "J1") (pin "16") (pinfunction "1_16") (pintype "passive"))
      (node (ref "J11") (pin "2") (pinfunction "S_2") (pintype "passive"))
      (node (ref "J12") (pin "2") (pinfunction "S_2") (pintype "passive"))
      (node (ref "J13") (pin "6") (pinfunction "6_6") (pintype "passive"))
      (node (ref "J14") (pin "5") (pinfunction "S_5") (pintype "passive"))
      (node (ref "J15") (pin "5") (pinfunction "S_5") (pintype "passive"))
      (node (ref "J16") (pin "5") (pinfunction "S_5") (pintype "passive"))
      (node (ref "J17") (pin "2") (pinfunction "S_2") (pintype "passive"))
      (node (ref "J18") (pin "1") (pinfunction "1_1") (pintype "passive"))
      (node (ref "J2") (pin "13") (pinfunction "1_13") (pintype "passive"))
      (node (ref "J2") (pin "3") (pinfunction "1_3") (pintype "passive"))
      (node (ref "J20") (pin "P3") (pinfunction "1_P3") (pintype "passive"))
      (node (ref "J20") (pin "P6") (pinfunction "1_P6") (pintype "passive"))
      (node (ref "J20") (pin "P9") (pinfunction "1_P9") (pintype "passive"))
      (node (ref "J21") (pin "P3") (pinfunction "1_P3") (pintype "passive"))
      (node (ref "J21") (pin "P6") (pinfunction "1_P6") (pintype "passive"))
      (node (ref "J21") (pin "P9") (pinfunction "1_P9") (pintype "passive"))
      (node (ref "J3") (pin "13") (pinfunction "1_13") (pintype "passive"))
      (node (ref "J3") (pin "3") (pinfunction "1_3") (pintype "passive"))
      (node (ref "J4") (pin "1") (pinfunction "1_1") (pintype "passive"))
      (node (ref "J4") (pin "11") (pinfunction "1_11") (pintype "passive"))
      (node (ref "J4") (pin "3") (pinfunction "1_3") (pintype "passive"))
      (node (ref "J4") (pin "5") (pinfunction "1_5") (pintype "passive"))
      (node (ref "J4") (pin "7") (pinfunction "1_7") (pintype "passive"))
      (node (ref "J4") (pin "9") (pinfunction "1_9") (pintype "passive"))
      (node (ref "J5") (pin "17") (pinfunction "17_17") (pintype "passive"))
      (node (ref "J5") (pin "4") (pinfunction "4_4") (pintype "passive"))
      (node (ref "J5") (pin "7") (pinfunction "7_7") (pintype "passive"))
      (node (ref "J6") (pin "1") (pinfunction "1_1") (pintype "passive"))
      (node (ref "J6") (pin "2") (pinfunction "1_2") (pintype "passive"))
      (node (ref "J6") (pin "43") (pinfunction "1_43") (pintype "passive"))
      (node (ref "J6") (pin "44") (pinfunction "1_44") (pintype "passive"))
      (node (ref "J6") (pin "45") (pinfunction "1_45") (pintype "passive"))
      (node (ref "J6") (pin "46") (pinfunction "1_46") (pintype "passive"))
      (node (ref "J7") (pin "2") (pinfunction "S_2") (pintype "passive"))
      (node (ref "J9") (pin "1") (pinfunction "S_1") (pintype "passive"))
      (node (ref "J9") (pin "3") (pinfunction "S_3") (pintype "passive"))
      (node (ref "LED1") (pin "C") (pinfunction "C_C") (pintype "passive"))
      (node (ref "LED2") (pin "C") (pinfunction "C_C") (pintype "passive"))
      (node (ref "LED5") (pin "C") (pinfunction "C_C") (pintype "passive"))
      (node (ref "LED6") (pin "C") (pinfunction "C_C") (pintype "passive"))
      (node (ref "LED7") (pin "C") (pinfunction "C_C") (pintype "passive"))
      (node (ref "OC1") (pin "3") (pinfunction "E_3") (pintype "passive"))
      (node (ref "Q2") (pin "2") (pinfunction "S_2") (pintype "passive"))
      (node (ref "Q4") (pin "2") (pinfunction "S_2") (pintype "passive"))
      (node (ref "Q5") (pin "2") (pinfunction "S_2") (pintype "passive"))
      (node (ref "Q6") (pin "2") (pinfunction "S_2") (pintype "passive"))
      (node (ref "Q7") (pin "2") (pinfunction "S_2") (pintype "passive"))
      (node (ref "R11") (pin "2") (pinfunction "2_2") (pintype "passive"))
      (node (ref "R15") (pin "1") (pinfunction "1_1") (pintype "passive"))
      (node (ref "R17") (pin "1") (pinfunction "1_1") (pintype "passive"))
      (node (ref "R40") (pin "1") (pinfunction "1_1") (pintype "passive"))
      (node (ref "R41") (pin "1") (pinfunction "1_1") (pintype "passive"))
      (node (ref "R42") (pin "1") (pinfunction "1_1") (pintype "passive"))
      (node (ref "R43") (pin "1") (pinfunction "1_1") (pintype "passive"))
      (node (ref "R67") (pin "1") (pinfunction "1_1") (pintype "passive"))
      (node (ref "R7") (pin "2") (pinfunction "2_2") (pintype "passive"))
      (node (ref "SENS1") (pin "1") (pinfunction "GND_1") (pintype "bidirectional"))
      (node (ref "SENS1") (pin "PAD") (pinfunction "PAD_PAD") (pintype "bidirectional"))
      (node (ref "SENS2") (pin "3") (pinfunction "GND_3") (pintype "bidirectional"))
      (node (ref "TP2") (pin "1") (pinfunction "P_1") (pintype "passive"))
      (node (ref "TP3") (pin "1") (pinfunction "P_1") (pintype "passive"))
      (node (ref "U1") (pin "1") (pinfunction "REF_1") (pintype "input"))
      (node (ref "U1") (pin "2") (pinfunction "GND_2") (pintype "input"))
      (node (ref "U10") (pin "1") (pinfunction "REF_1") (pintype "input"))
      (node (ref "U10") (pin "2") (pinfunction "GND_2") (pintype "input"))
      (node (ref "U11") (pin "1") (pinfunction "REF_1") (pintype "input"))
      (node (ref "U11") (pin "2") (pinfunction "GND_2") (pintype "input"))
      (node (ref "U2") (pin "1") (pinfunction "REF_1") (pintype "input"))
      (node (ref "U2") (pin "2") (pinfunction "GND_2") (pintype "input"))
      (node (ref "U3") (pin "1") (pinfunction "REF_1") (pintype "input"))
      (node (ref "U3") (pin "2") (pinfunction "GND_2") (pintype "input"))
      (node (ref "U4") (pin "11") (pinfunction "DAP_11") (pintype "bidirectional"))
      (node (ref "U4") (pin "5") (pinfunction "SGND_5") (pintype "bidirectional"))
      (node (ref "U4") (pin "7") (pinfunction "CSG_7") (pintype "bidirectional"))
      (node (ref "U5") (pin "1") (pinfunction "GND_1") (pintype "power_in"))
      (node (ref "U6") (pin "11") (pinfunction "GND_11") (pintype "input"))
      (node (ref "U6") (pin "32") (pinfunction "GND1_32") (pintype "input"))
      (node (ref "U6") (pin "62") (pinfunction "GND2_62") (pintype "input"))
      (node (ref "U6") (pin "81") (pinfunction "GND3_81") (pintype "input"))
      (node (ref "U6") (pin "99") (pinfunction "AGND_99") (pintype "input"))
      (node (ref "U7") (pin "11") (pinfunction "GND_11") (pintype "bidirectional"))
      (node (ref "U8") (pin "1") (pinfunction "A0_1") (pintype "input"))
      (node (ref "U8") (pin "2") (pinfunction "A1_2") (pintype "input"))
      (node (ref "U8") (pin "4") (pinfunction "VSS_4") (pintype "bidirectional"))
      (node (ref "U9") (pin "1") (pinfunction "REF_1") (pintype "input"))
      (node (ref "U9") (pin "2") (pinfunction "GND_2") (pintype "input"))
    )
    (net (code "125") (name "Net-(C5-Pad1)") (class "Default")
      (node (ref "C5") (pin "1") (pinfunction "1_1") (pintype "passive"))
      (node (ref "FB1") (pin "2") (pinfunction "2_2") (pintype "passive"))
      (node (ref "R3") (pin "2") (pinfunction "2_2") (pintype "passive"))
    )
    (net (code "126") (name "Net-(D1-C)") (class "Default")
      (node (ref "D1") (pin "4") (pinfunction "C_4") (pintype "passive"))
      (node (ref "R1") (pin "1") (pinfunction "1_1") (pintype "passive"))
      (node (ref "U2") (pin "4") (pinfunction "IN+_4") (pintype "input"))
    )
    (net (code "127") (name "Net-(D2-C)") (class "Default")
      (node (ref "D2") (pin "4") (pinfunction "C_4") (pintype "passive"))
      (node (ref "R2") (pin "1") (pinfunction "1_1") (pintype "passive"))
      (node (ref "U1") (pin "4") (pinfunction "IN+_4") (pintype "input"))
    )
    (net (code "128") (name "Net-(J11A-S)") (class "Default")
      (node (ref "D3") (pin "C") (pinfunction "C_C") (pintype "passive"))
      (node (ref "D4") (pin "C") (pinfunction "C_C") (pintype "passive"))
      (node (ref "D5") (pin "C") (pinfunction "C_C") (pintype "passive"))
      (node (ref "J11") (pin "1") (pinfunction "S_1") (pintype "passive"))
      (node (ref "Q1") (pin "1") (pinfunction "S_1") (pintype "passive"))
      (node (ref "Q1") (pin "2") (pinfunction "S_2") (pintype "passive"))
      (node (ref "Q1") (pin "3") (pinfunction "S_3") (pintype "passive"))
      (node (ref "Q3") (pin "1") (pinfunction "S_1") (pintype "passive"))
      (node (ref "Q3") (pin "2") (pinfunction "S_2") (pintype "passive"))
      (node (ref "Q3") (pin "3") (pinfunction "S_3") (pintype "passive"))
      (node (ref "R1") (pin "2") (pinfunction "2_2") (pintype "passive"))
      (node (ref "R2") (pin "2") (pinfunction "2_2") (pintype "passive"))
      (node (ref "R4") (pin "2") (pinfunction "2_2") (pintype "passive"))
      (node (ref "R6") (pin "2") (pinfunction "2_2") (pintype "passive"))
      (node (ref "U1") (pin "5") (pinfunction "IN-_5") (pintype "input"))
      (node (ref "U2") (pin "5") (pinfunction "IN-_5") (pintype "input"))
    )
    (net (code "129") (name "Net-(J12A-S)") (class "Default")
      (node (ref "C35") (pin "1") (pinfunction "1_1") (pintype "passive"))
      (node (ref "J12") (pin "1") (pinfunction "S_1") (pintype "passive"))
      (node (ref "OC1") (pin "4") (pinfunction "C_4") (pintype "passive"))
      (node (ref "R8") (pin "1") (pinfunction "1_1") (pintype "passive"))
    )
    (net (code "130") (name "Net-(J14E-S)") (class "Default")
      (node (ref "J14") (pin "1") (pinfunction "S_1") (pintype "passive"))
      (node (ref "R59") (pin "2") (pinfunction "2_2") (pintype "passive"))
      (node (ref "U9") (pin "5") (pinfunction "IN-_5") (pintype "input"))
    )
    (net (code "131") (name "Net-(J15E-S)") (class "Default")
      (node (ref "J15") (pin "1") (pinfunction "S_1") (pintype "passive"))
      (node (ref "R60") (pin "2") (pinfunction "2_2") (pintype "passive"))
      (node (ref "U10") (pin "5") (pinfunction "IN-_5") (pintype "input"))
    )
    (net (code "132") (name "Net-(J16E-S)") (class "Default")
      (node (ref "J16") (pin "1") (pinfunction "S_1") (pintype "passive"))
      (node (ref "R61") (pin "2") (pinfunction "2_2") (pintype "passive"))
      (node (ref "U11") (pin "5") (pinfunction "IN-_5") (pintype "input"))
    )
    (net (code "133") (name "Net-(J17A-S)") (class "Default")
      (node (ref "J17") (pin "1") (pinfunction "S_1") (pintype "passive"))
      (node (ref "Q2") (pin "3") (pinfunction "D_3") (pintype "passive"))
      (node (ref "R9") (pin "1") (pinfunction "1_1") (pintype "passive"))
    )
    (net (code "134") (name "Net-(J18B-1)") (class "Default")
      (node (ref "J18") (pin "2") (pinfunction "1_2") (pintype "passive"))
      (node (ref "R65") (pin "2") (pinfunction "2_2") (pintype "passive"))
    )
    (net (code "135") (name "Net-(J18C-1)") (class "Default")
      (node (ref "J18") (pin "3") (pinfunction "1_3") (pintype "passive"))
      (node (ref "R63") (pin "2") (pinfunction "2_2") (pintype "passive"))
    )
    (net (code "136") (name "Net-(J18D-1)") (class "Default")
      (node (ref "J18") (pin "4") (pinfunction "1_4") (pintype "passive"))
      (node (ref "R64") (pin "2") (pinfunction "2_2") (pintype "passive"))
    )
    (net (code "137") (name "Net-(J20B-1)") (class "Default")
      (node (ref "J20") (pin "P2") (pinfunction "1_P2") (pintype "passive"))
      (node (ref "J20") (pin "P5") (pinfunction "1_P5") (pintype "passive"))
      (node (ref "J20") (pin "P8") (pinfunction "1_P8") (pintype "passive"))
      (node (ref "J21") (pin "P2") (pinfunction "1_P2") (pintype "passive"))
      (node (ref "J21") (pin "P5") (pinfunction "1_P5") (pintype "passive"))
      (node (ref "J21") (pin "P8") (pinfunction "1_P8") (pintype "passive"))
      (node (ref "J7") (pin "1") (pinfunction "S_1") (pintype "passive"))
    )
    (net (code "138") (name "Net-(L1-1)") (class "Default")
      (node (ref "C12") (pin "2") (pinfunction "2_2") (pintype "passive"))
      (node (ref "D6") (pin "C") (pinfunction "C_C") (pintype "passive"))
      (node (ref "L1") (pin "P$1") (pinfunction "1_P$1") (pintype "passive"))
      (node (ref "U4") (pin "9") (pinfunction "SW_9") (pintype "bidirectional"))
    )
    (net (code "139") (name "Net-(LED1-PadA)") (class "Default")
      (node (ref "LED1") (pin "A") (pinfunction "A_A") (pintype "passive"))
      (node (ref "R18") (pin "2") (pinfunction "2_2") (pintype "passive"))
    )
    (net (code "140") (name "Net-(LED2-PadA)") (class "Default")
      (node (ref "LED2") (pin "A") (pinfunction "A_A") (pintype "passive"))
      (node (ref "R19") (pin "2") (pinfunction "2_2") (pintype "passive"))
    )
    (net (code "141") (name "Net-(LED3-PadC)") (class "Default")
      (node (ref "LED3") (pin "C") (pinfunction "C_C") (pintype "passive"))
      (node (ref "R21") (pin "1") (pinfunction "1_1") (pintype "passive"))
    )
    (net (code "142") (name "Net-(LED4-PadC)") (class "Default")
      (node (ref "LED4") (pin "C") (pinfunction "C_C") (pintype "passive"))
      (node (ref "R22") (pin "1") (pinfunction "1_1") (pintype "passive"))
    )
    (net (code "143") (name "Net-(LED5-PadA)") (class "Default")
      (node (ref "LED5") (pin "A") (pinfunction "A_A") (pintype "passive"))
      (node (ref "R23") (pin "2") (pinfunction "2_2") (pintype "passive"))
    )
    (net (code "144") (name "Net-(LED6-PadA)") (class "Default")
      (node (ref "LED6") (pin "A") (pinfunction "A_A") (pintype "passive"))
      (node (ref "R63") (pin "1") (pinfunction "1_1") (pintype "passive"))
    )
    (net (code "145") (name "Net-(LED7-PadA)") (class "Default")
      (node (ref "LED7") (pin "A") (pinfunction "A_A") (pintype "passive"))
      (node (ref "R64") (pin "1") (pinfunction "1_1") (pintype "passive"))
    )
    (net (code "146") (name "Net-(LED8-PadC)") (class "Default")
      (node (ref "LED8") (pin "C") (pinfunction "C_C") (pintype "passive"))
      (node (ref "R65") (pin "1") (pinfunction "1_1") (pintype "passive"))
    )
    (net (code "147") (name "Net-(OC1-IN-A)") (class "Default")
      (node (ref "OC1") (pin "1") (pinfunction "IN-A_1") (pintype "passive"))
      (node (ref "R3") (pin "1") (pinfunction "1_1") (pintype "passive"))
    )
    (net (code "148") (name "Net-(Q1-G)") (class "Default")
      (node (ref "D4") (pin "A") (pinfunction "A_A") (pintype "passive"))
      (node (ref "Q1") (pin "4") (pinfunction "G_4") (pintype "passive"))
      (node (ref "R4") (pin "1") (pinfunction "1_1") (pintype "passive"))
      (node (ref "R8") (pin "2") (pinfunction "2_2") (pintype "passive"))
    )
    (net (code "149") (name "Net-(Q2-G)") (class "Default")
      (node (ref "Q2") (pin "1") (pinfunction "G_1") (pintype "passive"))
      (node (ref "R5") (pin "1") (pinfunction "1_1") (pintype "passive"))
      (node (ref "R7") (pin "1") (pinfunction "1_1") (pintype "passive"))
    )
    (net (code "150") (name "Net-(Q3-G)") (class "Default")
      (node (ref "D5") (pin "A") (pinfunction "A_A") (pintype "passive"))
      (node (ref "Q3") (pin "4") (pinfunction "G_4") (pintype "passive"))
      (node (ref "R6") (pin "1") (pinfunction "1_1") (pintype "passive"))
      (node (ref "R9") (pin "2") (pinfunction "2_2") (pintype "passive"))
    )
    (net (code "151") (name "Net-(Q4-G)") (class "Default")
      (node (ref "Q4") (pin "1") (pinfunction "G_1") (pintype "passive"))
      (node (ref "R36") (pin "2") (pinfunction "2_2") (pintype "passive"))
      (node (ref "R40") (pin "2") (pinfunction "2_2") (pintype "passive"))
    )
    (net (code "152") (name "Net-(Q5-G)") (class "Default")
      (node (ref "Q5") (pin "1") (pinfunction "G_1") (pintype "passive"))
      (node (ref "R37") (pin "2") (pinfunction "2_2") (pintype "passive"))
      (node (ref "R41") (pin "2") (pinfunction "2_2") (pintype "passive"))
    )
    (net (code "153") (name "Net-(Q6-G)") (class "Default")
      (node (ref "Q6") (pin "1") (pinfunction "G_1") (pintype "passive"))
      (node (ref "R38") (pin "2") (pinfunction "2_2") (pintype "passive"))
      (node (ref "R42") (pin "2") (pinfunction "2_2") (pintype "passive"))
    )
    (net (code "154") (name "Net-(Q7-G)") (class "Default")
      (node (ref "Q7") (pin "1") (pinfunction "G_1") (pintype "passive"))
      (node (ref "R39") (pin "2") (pinfunction "2_2") (pintype "passive"))
      (node (ref "R43") (pin "2") (pinfunction "2_2") (pintype "passive"))
    )
    (net (code "155") (name "Net-(SENS1-OUT)") (class "Default")
      (node (ref "R45") (pin "1") (pinfunction "1_1") (pintype "passive"))
      (node (ref "SENS1") (pin "2") (pinfunction "OUT_2") (pintype "output"))
    )
    (net (code "156") (name "Net-(SENS2-VOUT)") (class "Default")
      (node (ref "R44") (pin "1") (pinfunction "1_1") (pintype "passive"))
      (node (ref "SENS2") (pin "2") (pinfunction "VOUT_2") (pintype "output"))
    )
    (net (code "157") (name "Net-(TP20-P)") (class "Default")
      (node (ref "J5") (pin "20") (pinfunction "20_20") (pintype "passive"))
      (node (ref "TP20") (pin "1") (pinfunction "P_1") (pintype "passive"))
    )
    (net (code "158") (name "Net-(TP21-P)") (class "Default")
      (node (ref "J5") (pin "21") (pinfunction "21_21") (pintype "passive"))
      (node (ref "TP21") (pin "1") (pinfunction "P_1") (pintype "passive"))
    )
    (net (code "159") (name "Net-(TP22-P)") (class "Default")
      (node (ref "J5") (pin "22") (pinfunction "22_22") (pintype "passive"))
      (node (ref "TP22") (pin "1") (pinfunction "P_1") (pintype "passive"))
    )
    (net (code "160") (name "Net-(TP23-P)") (class "Default")
      (node (ref "J5") (pin "23") (pinfunction "23_23") (pintype "passive"))
      (node (ref "TP23") (pin "1") (pinfunction "P_1") (pintype "passive"))
    )
    (net (code "161") (name "Net-(TP24-P)") (class "Default")
      (node (ref "J5") (pin "24") (pinfunction "24_24") (pintype "passive"))
      (node (ref "TP24") (pin "1") (pinfunction "P_1") (pintype "passive"))
    )
    (net (code "162") (name "Net-(TP25-P)") (class "Default")
      (node (ref "J5") (pin "25") (pinfunction "25_25") (pintype "passive"))
      (node (ref "TP25") (pin "1") (pinfunction "P_1") (pintype "passive"))
    )
    (net (code "163") (name "Net-(U3-IN+)") (class "Default")
      (node (ref "Q1") (pin "5") (pinfunction "D_5") (pintype "passive"))
      (node (ref "Q1") (pin "6") (pinfunction "D_6") (pintype "passive"))
      (node (ref "Q1") (pin "7") (pinfunction "D_7") (pintype "passive"))
      (node (ref "Q1") (pin "8") (pinfunction "D_8") (pintype "passive"))
      (node (ref "R10") (pin "1") (pinfunction "1_1") (pintype "passive"))
      (node (ref "R12") (pin "1") (pinfunction "1_1") (pintype "passive"))
      (node (ref "U3") (pin "4") (pinfunction "IN+_4") (pintype "input"))
    )
    (net (code "164") (name "Net-(U4-BST)") (class "Default")
      (node (ref "C12") (pin "1") (pinfunction "1_1") (pintype "passive"))
      (node (ref "U4") (pin "10") (pinfunction "BST_10") (pintype "bidirectional"))
    )
    (net (code "165") (name "Net-(U4-CS)") (class "Default")
      (node (ref "D6") (pin "A") (pinfunction "A_A") (pintype "passive"))
      (node (ref "R15") (pin "2") (pinfunction "2_2") (pintype "passive"))
      (node (ref "U4") (pin "8") (pinfunction "CS_8") (pintype "bidirectional"))
    )
    (net (code "166") (name "Net-(U4-FB)") (class "Default")
      (node (ref "R16") (pin "1") (pinfunction "1_1") (pintype "passive"))
      (node (ref "R17") (pin "2") (pinfunction "2_2") (pintype "passive"))
      (node (ref "U4") (pin "6") (pinfunction "FB_6") (pintype "bidirectional"))
    )
    (net (code "167") (name "Net-(U4-PGD)") (class "Default")
      (node (ref "R13") (pin "1") (pinfunction "1_1") (pintype "passive"))
      (node (ref "U4") (pin "3") (pinfunction "PGD_3") (pintype "bidirectional"))
    )
    (net (code "168") (name "Net-(U4-RT)") (class "Default")
      (node (ref "R14") (pin "1") (pinfunction "1_1") (pintype "passive"))
      (node (ref "U4") (pin "2") (pinfunction "RT_2") (pintype "bidirectional"))
    )
    (net (code "169") (name "Net-(U4-SS)") (class "Default")
      (node (ref "C11") (pin "1") (pinfunction "1_1") (pintype "passive"))
      (node (ref "U4") (pin "4") (pinfunction "SS_4") (pintype "bidirectional"))
    )
    (net (code "170") (name "Net-(U4-VIN)") (class "Default")
      (node (ref "C10") (pin "1") (pinfunction "1_1") (pintype "passive"))
      (node (ref "C8") (pin "1") (pinfunction "1_1") (pintype "passive"))
      (node (ref "C9") (pin "1") (pinfunction "1_1") (pintype "passive"))
      (node (ref "F1") (pin "2") (pinfunction "2_2") (pintype "passive"))
      (node (ref "R14") (pin "2") (pinfunction "2_2") (pintype "passive"))
      (node (ref "U4") (pin "1") (pinfunction "VIN_1") (pintype "input"))
    )
    (net (code "171") (name "Net-(U6-XTAL1)") (class "Default")
      (node (ref "C20") (pin "1") (pinfunction "1_1") (pintype "passive"))
      (node (ref "U6") (pin "34") (pinfunction "XTAL1_34") (pintype "input"))
      (node (ref "X1") (pin "1") (pinfunction "1_1") (pintype "passive"))
    )
    (net (code "172") (name "Net-(U6-XTAL2)") (class "Default")
      (node (ref "C19") (pin "1") (pinfunction "1_1") (pintype "passive"))
      (node (ref "U6") (pin "33") (pinfunction "XTAL2_33") (pintype "output"))
      (node (ref "X1") (pin "2") (pinfunction "2_2") (pintype "passive"))
    )
    (net (code "173") (name "Net-(U7-A8)") (class "Default")
      (node (ref "R62") (pin "1") (pinfunction "1_1") (pintype "passive"))
      (node (ref "U7") (pin "9") (pinfunction "A8_9") (pintype "bidirectional"))
    )
    (net (code "174") (name "Net-(U7-OE)") (class "Default")
      (node (ref "R47") (pin "1") (pinfunction "1_1") (pintype "passive"))
      (node (ref "R48") (pin "1") (pinfunction "1_1") (pintype "passive"))
      (node (ref "U7") (pin "10") (pinfunction "OE_10") (pintype "bidirectional"))
    )
    (net (code "175") (name "Net-(U8-A2)") (class "Default")
      (node (ref "R51") (pin "1") (pinfunction "1_1") (pintype "passive"))
      (node (ref "U8") (pin "3") (pinfunction "A2_3") (pintype "input"))
    )
    (net (code "176") (name "Net-(U8-WP)") (class "Default")
      (node (ref "R52") (pin "1") (pinfunction "1_1") (pintype "passive"))
      (node (ref "R67") (pin "2") (pinfunction "2_2") (pintype "passive"))
      (node (ref "U8") (pin "7") (pinfunction "WP_7") (pintype "bidirectional"))
    )
    (net (code "177") (name "Net-(U9-VOUT)") (class "Default")
      (node (ref "R49") (pin "1") (pinfunction "1_1") (pintype "passive"))
      (node (ref "U9") (pin "6") (pinfunction "VOUT_6") (pintype "output"))
    )
    (net (code "178") (name "Net-(U10-VOUT)") (class "Default")
      (node (ref "R50") (pin "1") (pinfunction "1_1") (pintype "passive"))
      (node (ref "U10") (pin "6") (pinfunction "VOUT_6") (pintype "output"))
    )
    (net (code "179") (name "Net-(U11-VOUT)") (class "Default")
      (node (ref "R66") (pin "1") (pinfunction "1_1") (pintype "passive"))
      (node (ref "U11") (pin "6") (pinfunction "VOUT_6") (pintype "output"))
    )
    (net (code "180") (name "PWM_1+") (class "Default")
      (node (ref "D7") (pin "C") (pinfunction "C_C") (pintype "passive"))
      (node (ref "J1") (pin "1") (pinfunction "1_1") (pintype "passive"))
      (node (ref "R24") (pin "2") (pinfunction "2_2") (pintype "passive"))
      (node (ref "R25") (pin "2") (pinfunction "2_2") (pintype "passive"))
      (node (ref "R26") (pin "2") (pinfunction "2_2") (pintype "passive"))
    )
    (net (code "181") (name "PWM_1-") (class "Default")
      (node (ref "D7") (pin "A") (pinfunction "A_A") (pintype "passive"))
      (node (ref "J1") (pin "2") (pinfunction "1_2") (pintype "passive"))
      (node (ref "Q4") (pin "3") (pinfunction "D_3") (pintype "passive"))
    )
    (net (code "182") (name "PWM_2+") (class "Default")
      (node (ref "D8") (pin "C") (pinfunction "C_C") (pintype "passive"))
      (node (ref "J1") (pin "3") (pinfunction "1_3") (pintype "passive"))
      (node (ref "R27") (pin "2") (pinfunction "2_2") (pintype "passive"))
      (node (ref "R28") (pin "2") (pinfunction "2_2") (pintype "passive"))
      (node (ref "R29") (pin "2") (pinfunction "2_2") (pintype "passive"))
    )
    (net (code "183") (name "PWM_2-") (class "Default")
      (node (ref "D8") (pin "A") (pinfunction "A_A") (pintype "passive"))
      (node (ref "J1") (pin "4") (pinfunction "1_4") (pintype "passive"))
      (node (ref "Q5") (pin "3") (pinfunction "D_3") (pintype "passive"))
    )
    (net (code "184") (name "PWM_3+") (class "Default")
      (node (ref "D9") (pin "C") (pinfunction "C_C") (pintype "passive"))
      (node (ref "J1") (pin "5") (pinfunction "1_5") (pintype "passive"))
      (node (ref "R30") (pin "2") (pinfunction "2_2") (pintype "passive"))
      (node (ref "R31") (pin "2") (pinfunction "2_2") (pintype "passive"))
      (node (ref "R32") (pin "2") (pinfunction "2_2") (pintype "passive"))
    )
    (net (code "185") (name "PWM_3-") (class "Default")
      (node (ref "D9") (pin "A") (pinfunction "A_A") (pintype "passive"))
      (node (ref "J1") (pin "6") (pinfunction "1_6") (pintype "passive"))
      (node (ref "Q6") (pin "3") (pinfunction "D_3") (pintype "passive"))
    )
    (net (code "186") (name "PWM_4+") (class "Default")
      (node (ref "D10") (pin "C") (pinfunction "C_C") (pintype "passive"))
      (node (ref "J1") (pin "7") (pinfunction "1_7") (pintype "passive"))
      (node (ref "R33") (pin "2") (pinfunction "2_2") (pintype "passive"))
      (node (ref "R34") (pin "2") (pinfunction "2_2") (pintype "passive"))
      (node (ref "R35") (pin "2") (pinfunction "2_2") (pintype "passive"))
    )
    (net (code "187") (name "PWM_4-") (class "Default")
      (node (ref "D10") (pin "A") (pinfunction "A_A") (pintype "passive"))
      (node (ref "J1") (pin "8") (pinfunction "1_8") (pintype "passive"))
      (node (ref "Q7") (pin "3") (pinfunction "D_3") (pintype "passive"))
    )
    (net (code "188") (name "RESET_N") (class "Default")
      (node (ref "J13") (pin "5") (pinfunction "5_5") (pintype "passive"))
      (node (ref "R20") (pin "2") (pinfunction "2_2") (pintype "passive"))
      (node (ref "U6") (pin "30") (pinfunction "RESET_30") (pintype "input"))
      (node (ref "U7") (pin "13") (pinfunction "B7_13") (pintype "bidirectional"))
    )
    (net (code "189") (name "TETHER_A") (class "Default")
      (node (ref "FB1") (pin "1") (pinfunction "1_1") (pintype "passive"))
      (node (ref "J10") (pin "1") (pinfunction "S_1") (pintype "passive"))
      (node (ref "J19") (pin "1") (pinfunction "1_1") (pintype "passive"))
      (node (ref "J19") (pin "2") (pinfunction "1_2") (pintype "passive"))
      (node (ref "J5") (pin "18") (pinfunction "18_18") (pintype "passive"))
    )
    (net (code "190") (name "TETHER_B") (class "Default")
      (node (ref "C5") (pin "2") (pinfunction "2_2") (pintype "passive"))
      (node (ref "J10") (pin "3") (pinfunction "S_3") (pintype "passive"))
      (node (ref "J19") (pin "5") (pinfunction "1_5") (pintype "passive"))
      (node (ref "J19") (pin "6") (pinfunction "1_6") (pintype "passive"))
      (node (ref "J5") (pin "19") (pinfunction "19_19") (pintype "passive"))
      (node (ref "OC1") (pin "2") (pinfunction "IN-B_2") (pintype "passive"))
    )
    (net (code "191") (name "V_BAT") (class "Default")
      (node (ref "F1") (pin "1") (pinfunction "1_1") (pintype "passive"))
      (node (ref "R12") (pin "2") (pinfunction "2_2") (pintype "passive"))
      (node (ref "R26") (pin "1") (pinfunction "1_1") (pintype "passive"))
      (node (ref "R29") (pin "1") (pinfunction "1_1") (pintype "passive"))
      (node (ref "R32") (pin "1") (pinfunction "1_1") (pintype "passive"))
      (node (ref "R35") (pin "1") (pinfunction "1_1") (pintype "passive"))
      (node (ref "U3") (pin "5") (pinfunction "IN-_5") (pintype "input"))
    )
    (net (code "192") (name "unconnected-(J10B-S-Pad2)") (class "Default")
      (node (ref "J10") (pin "2") (pinfunction "S_2") (pintype "passive"))
    )
    (net (code "193") (name "unconnected-(J19C-1-Pad3)") (class "Default")
      (node (ref "J19") (pin "3") (pinfunction "1_3") (pintype "passive"))
    )
    (net (code "194") (name "unconnected-(J19D-1-Pad4)") (class "Default")
      (node (ref "J19") (pin "4") (pinfunction "1_4") (pintype "passive"))
    )
    (net (code "195") (name "unconnected-(U6-(CLKO{slash}ICP3{slash}INT7)PE7-Pad9)") (class "Default")
      (node (ref "U6") (pin "9") (pinfunction "(CLKO/ICP3/INT7)PE7_9") (pintype "bidirectional"))
    )
    (net (code "196") (name "unconnected-(U6-(ICP1)PD4-Pad47)") (class "Default")
      (node (ref "U6") (pin "47") (pinfunction "(ICP1)PD4_47") (pintype "bidirectional"))
    )
    (net (code "197") (name "unconnected-(U6-(T1)PD6-Pad49)") (class "Default")
      (node (ref "U6") (pin "49") (pinfunction "(T1)PD6_49") (pintype "bidirectional"))
    )
    (net (code "198") (name "unconnected-(U6-(T3{slash}INT6)PE6-Pad8)") (class "Default")
      (node (ref "U6") (pin "8") (pinfunction "(T3/INT6)PE6_8") (pintype "bidirectional"))
    )
    (net (code "199") (name "unconnected-(U6-(TOSC1)PG4-Pad29)") (class "Default")
      (node (ref "U6") (pin "29") (pinfunction "(TOSC1)PG4_29") (pintype "bidirectional"))
    )
    (net (code "200") (name "unconnected-(U6-(TOSC2)PG3-Pad28)") (class "Default")
      (node (ref "U6") (pin "28") (pinfunction "(TOSC2)PG3_28") (pintype "bidirectional"))
    )
    (net (code "201") (name "unconnected-(U6-(XCK0{slash}AIN0)PE2-Pad4)") (class "Default")
      (node (ref "U6") (pin "4") (pinfunction "(XCK0/AIN0)PE2_4") (pintype "bidirectional"))
    )
    (net (code "202") (name "unconnected-(U6-(XCK1)PD5-Pad48)") (class "Default")
      (node (ref "U6") (pin "48") (pinfunction "(XCK1)PD5_48") (pintype "bidirectional"))
    )
    (net (code "203") (name "unconnected-(U6-PH2(XCK2)-Pad14)") (class "Default")
      (node (ref "U6") (pin "14") (pinfunction "PH2(XCK2)_14") (pintype "bidirectional"))
    )
    (net (code "204") (name "unconnected-(U6-PH7(T4)-Pad27)") (class "Default")
      (node (ref "U6") (pin "27") (pinfunction "PH7(T4)_27") (pintype "bidirectional"))
    )
    (net (code "205") (name "unconnected-(U6-PJ2(XCK3{slash}PCINT11)-Pad65)") (class "Default")
      (node (ref "U6") (pin "65") (pinfunction "PJ2(XCK3/PCINT11)_65") (pintype "bidirectional"))
    )
    (net (code "206") (name "unconnected-(U6-PJ3(PCINT12)-Pad66)") (class "Default")
      (node (ref "U6") (pin "66") (pinfunction "PJ3(PCINT12)_66") (pintype "bidirectional"))
    )
    (net (code "207") (name "unconnected-(U6-PJ4(PCINT13)-Pad67)") (class "Default")
      (node (ref "U6") (pin "67") (pinfunction "PJ4(PCINT13)_67") (pintype "bidirectional"))
    )
    (net (code "208") (name "unconnected-(U6-PJ5(PCINT14)-Pad68)") (class "Default")
      (node (ref "U6") (pin "68") (pinfunction "PJ5(PCINT14)_68") (pintype "bidirectional"))
    )
    (net (code "209") (name "unconnected-(U6-PJ6(PCINT15)-Pad69)") (class "Default")
      (node (ref "U6") (pin "69") (pinfunction "PJ6(PCINT15)_69") (pintype "bidirectional"))
    )
    (net (code "210") (name "unconnected-(U6-PJ7-Pad79)") (class "Default")
      (node (ref "U6") (pin "79") (pinfunction "PJ7_79") (pintype "bidirectional"))
    )
    (net (code "211") (name "unconnected-(U7-B8-Pad12)") (class "Default")
      (node (ref "U7") (pin "12") (pinfunction "B8_12") (pintype "bidirectional"))
    )
  )
)
